# E-P-206-R1_2_Fuel_Cell_Control_Board_to_.net
KiCad netlist of a schematic drawn in EAGLE
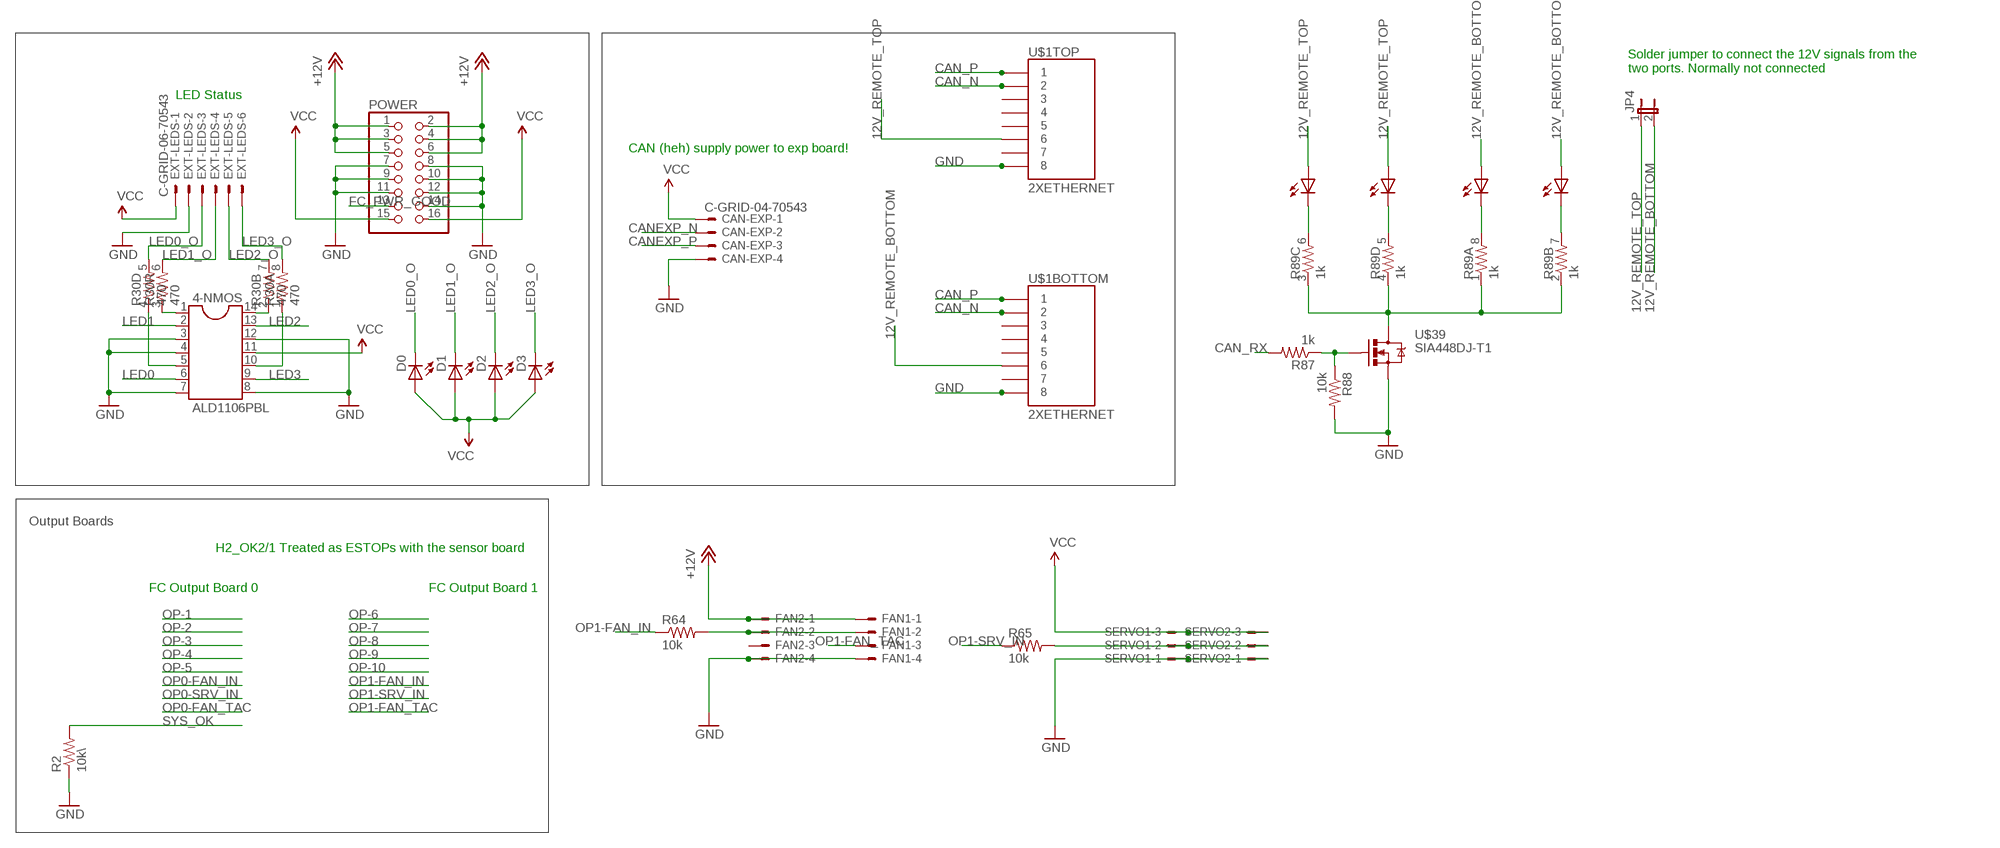
[diagram p0: schematic, sheet 1]
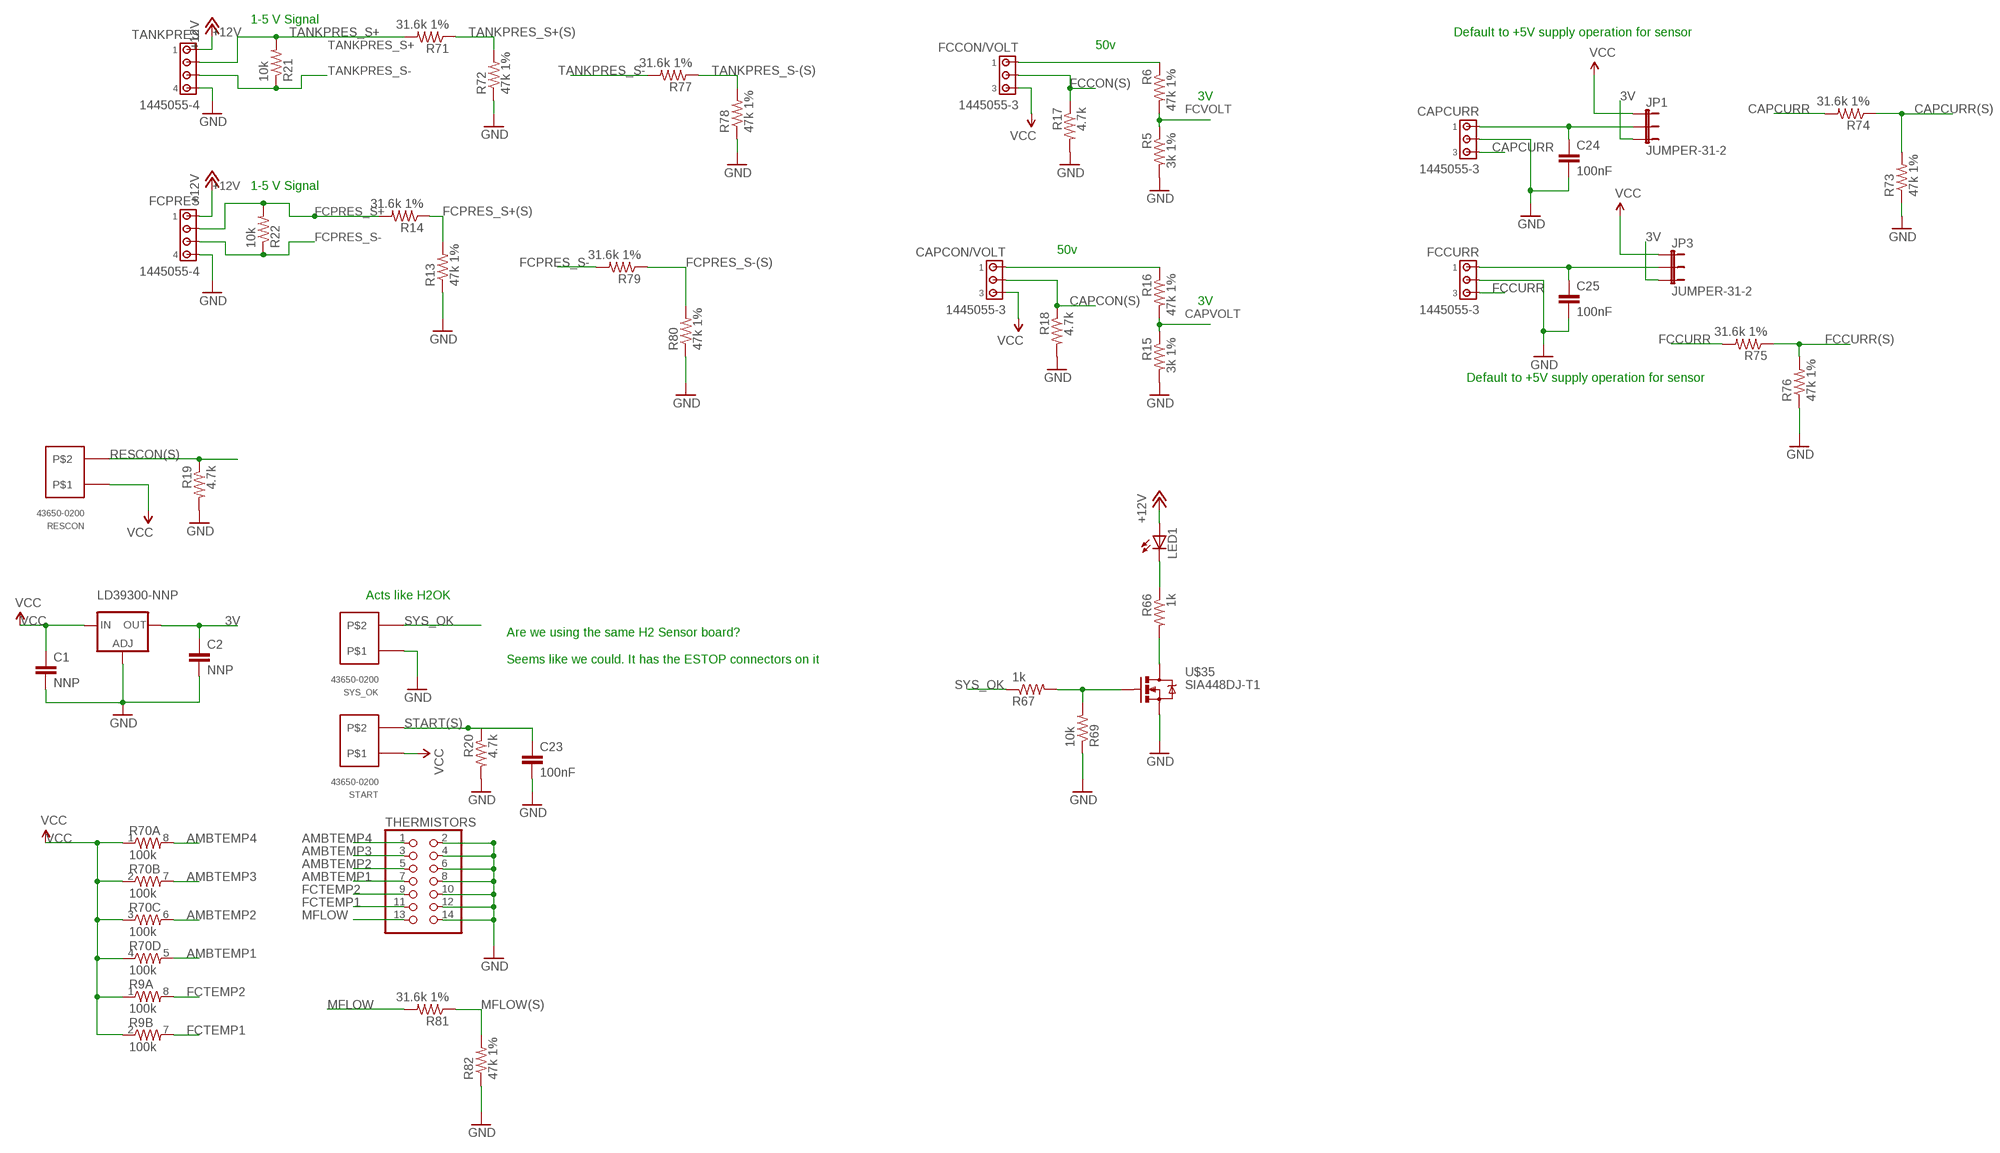
[diagram p1: schematic, sheet 2]
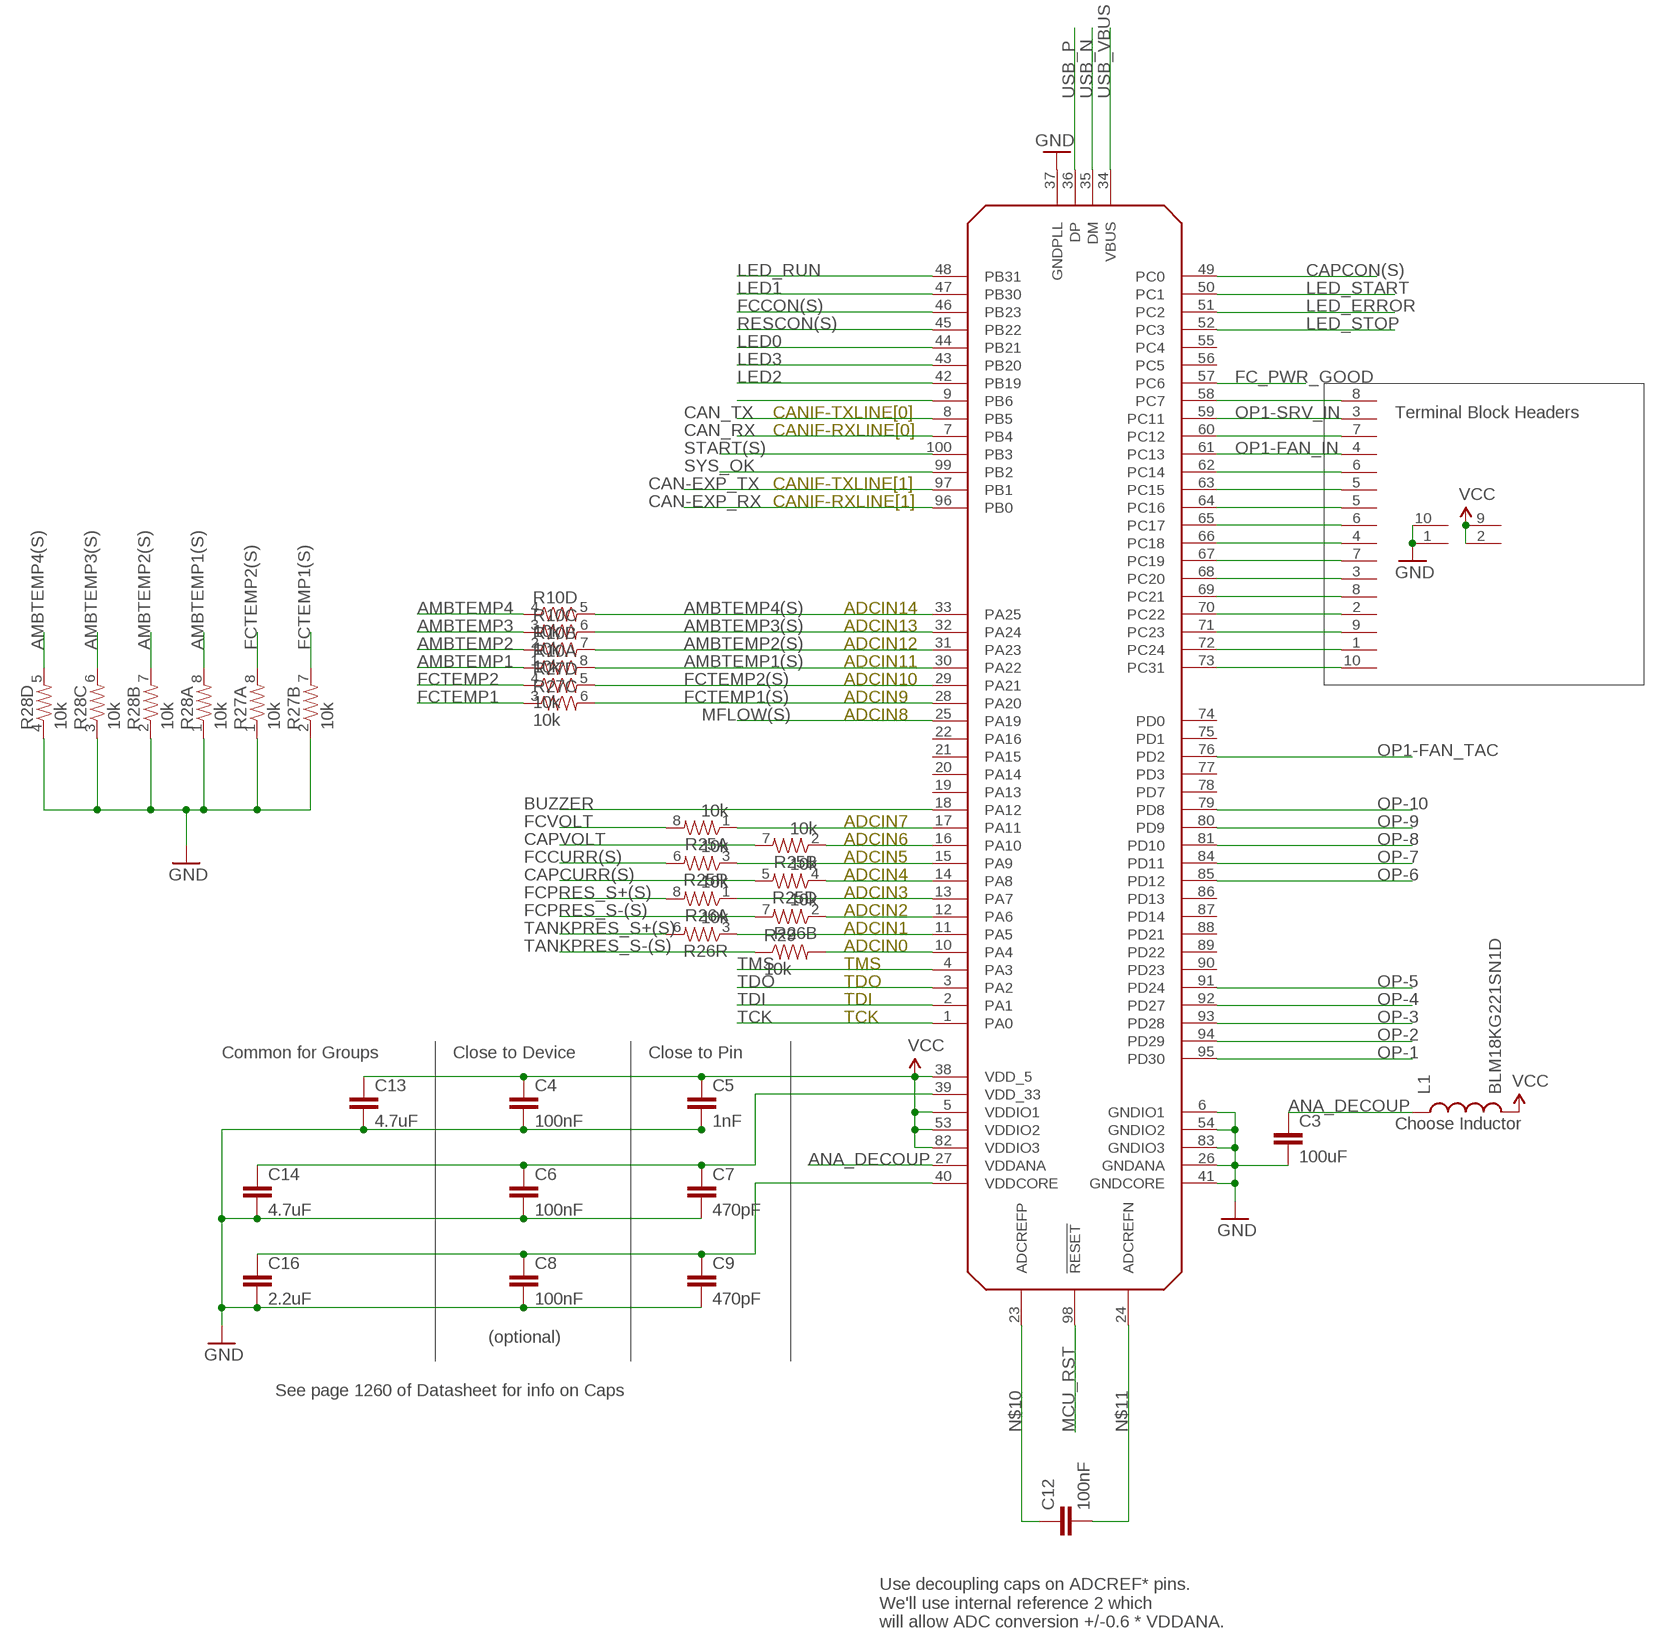
[diagram p2: schematic, sheet 3, part 1 of 2]
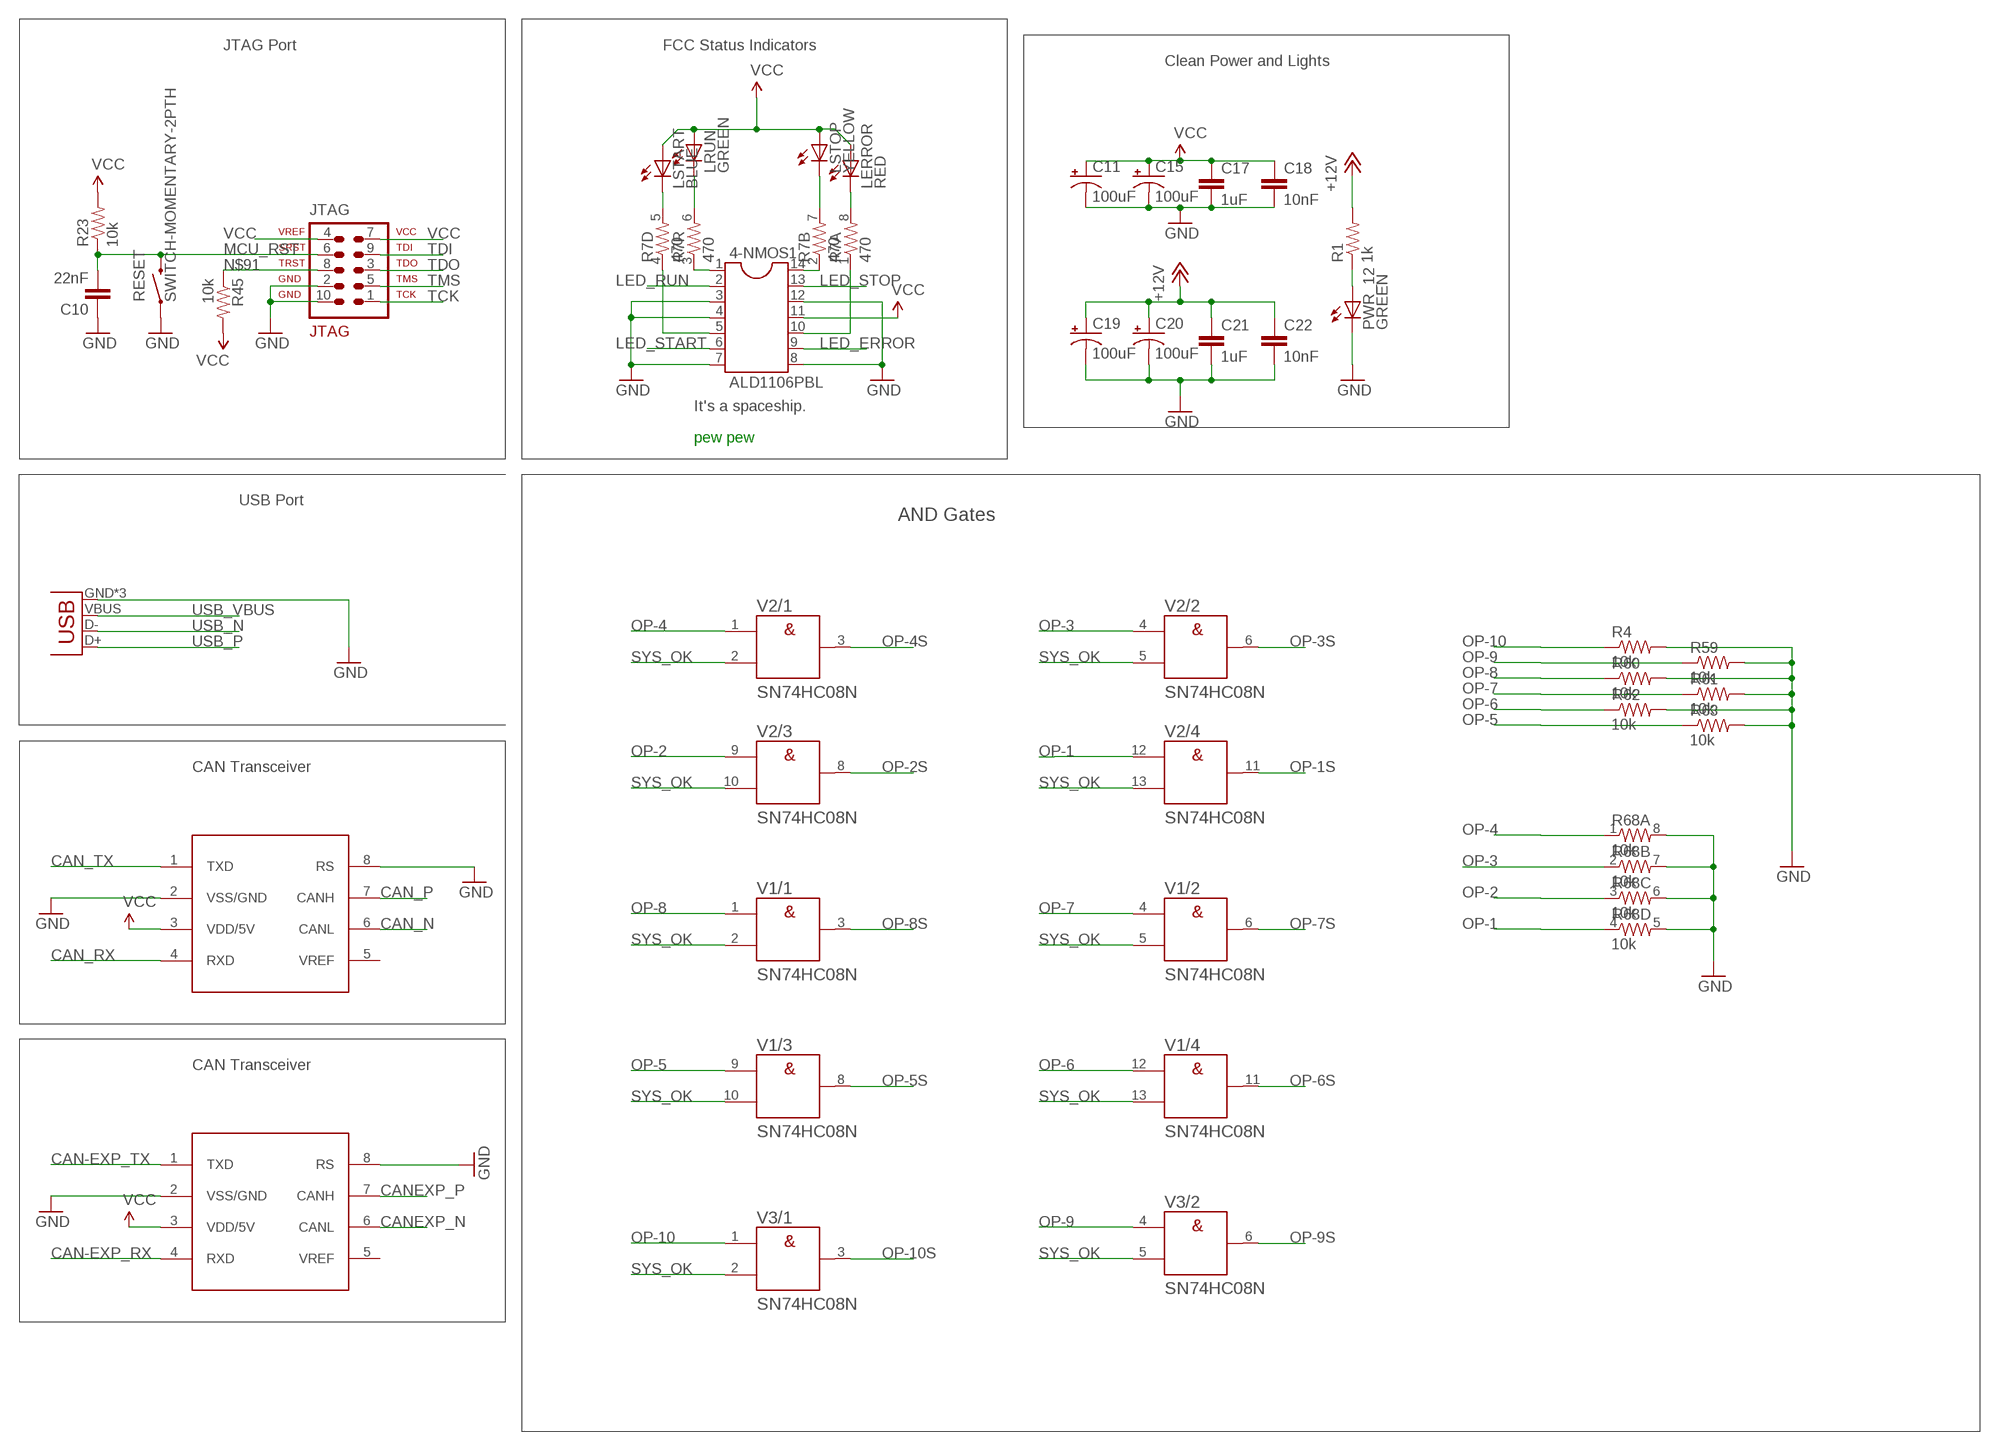
[diagram p3: schematic, sheet 3, part 2 of 2]
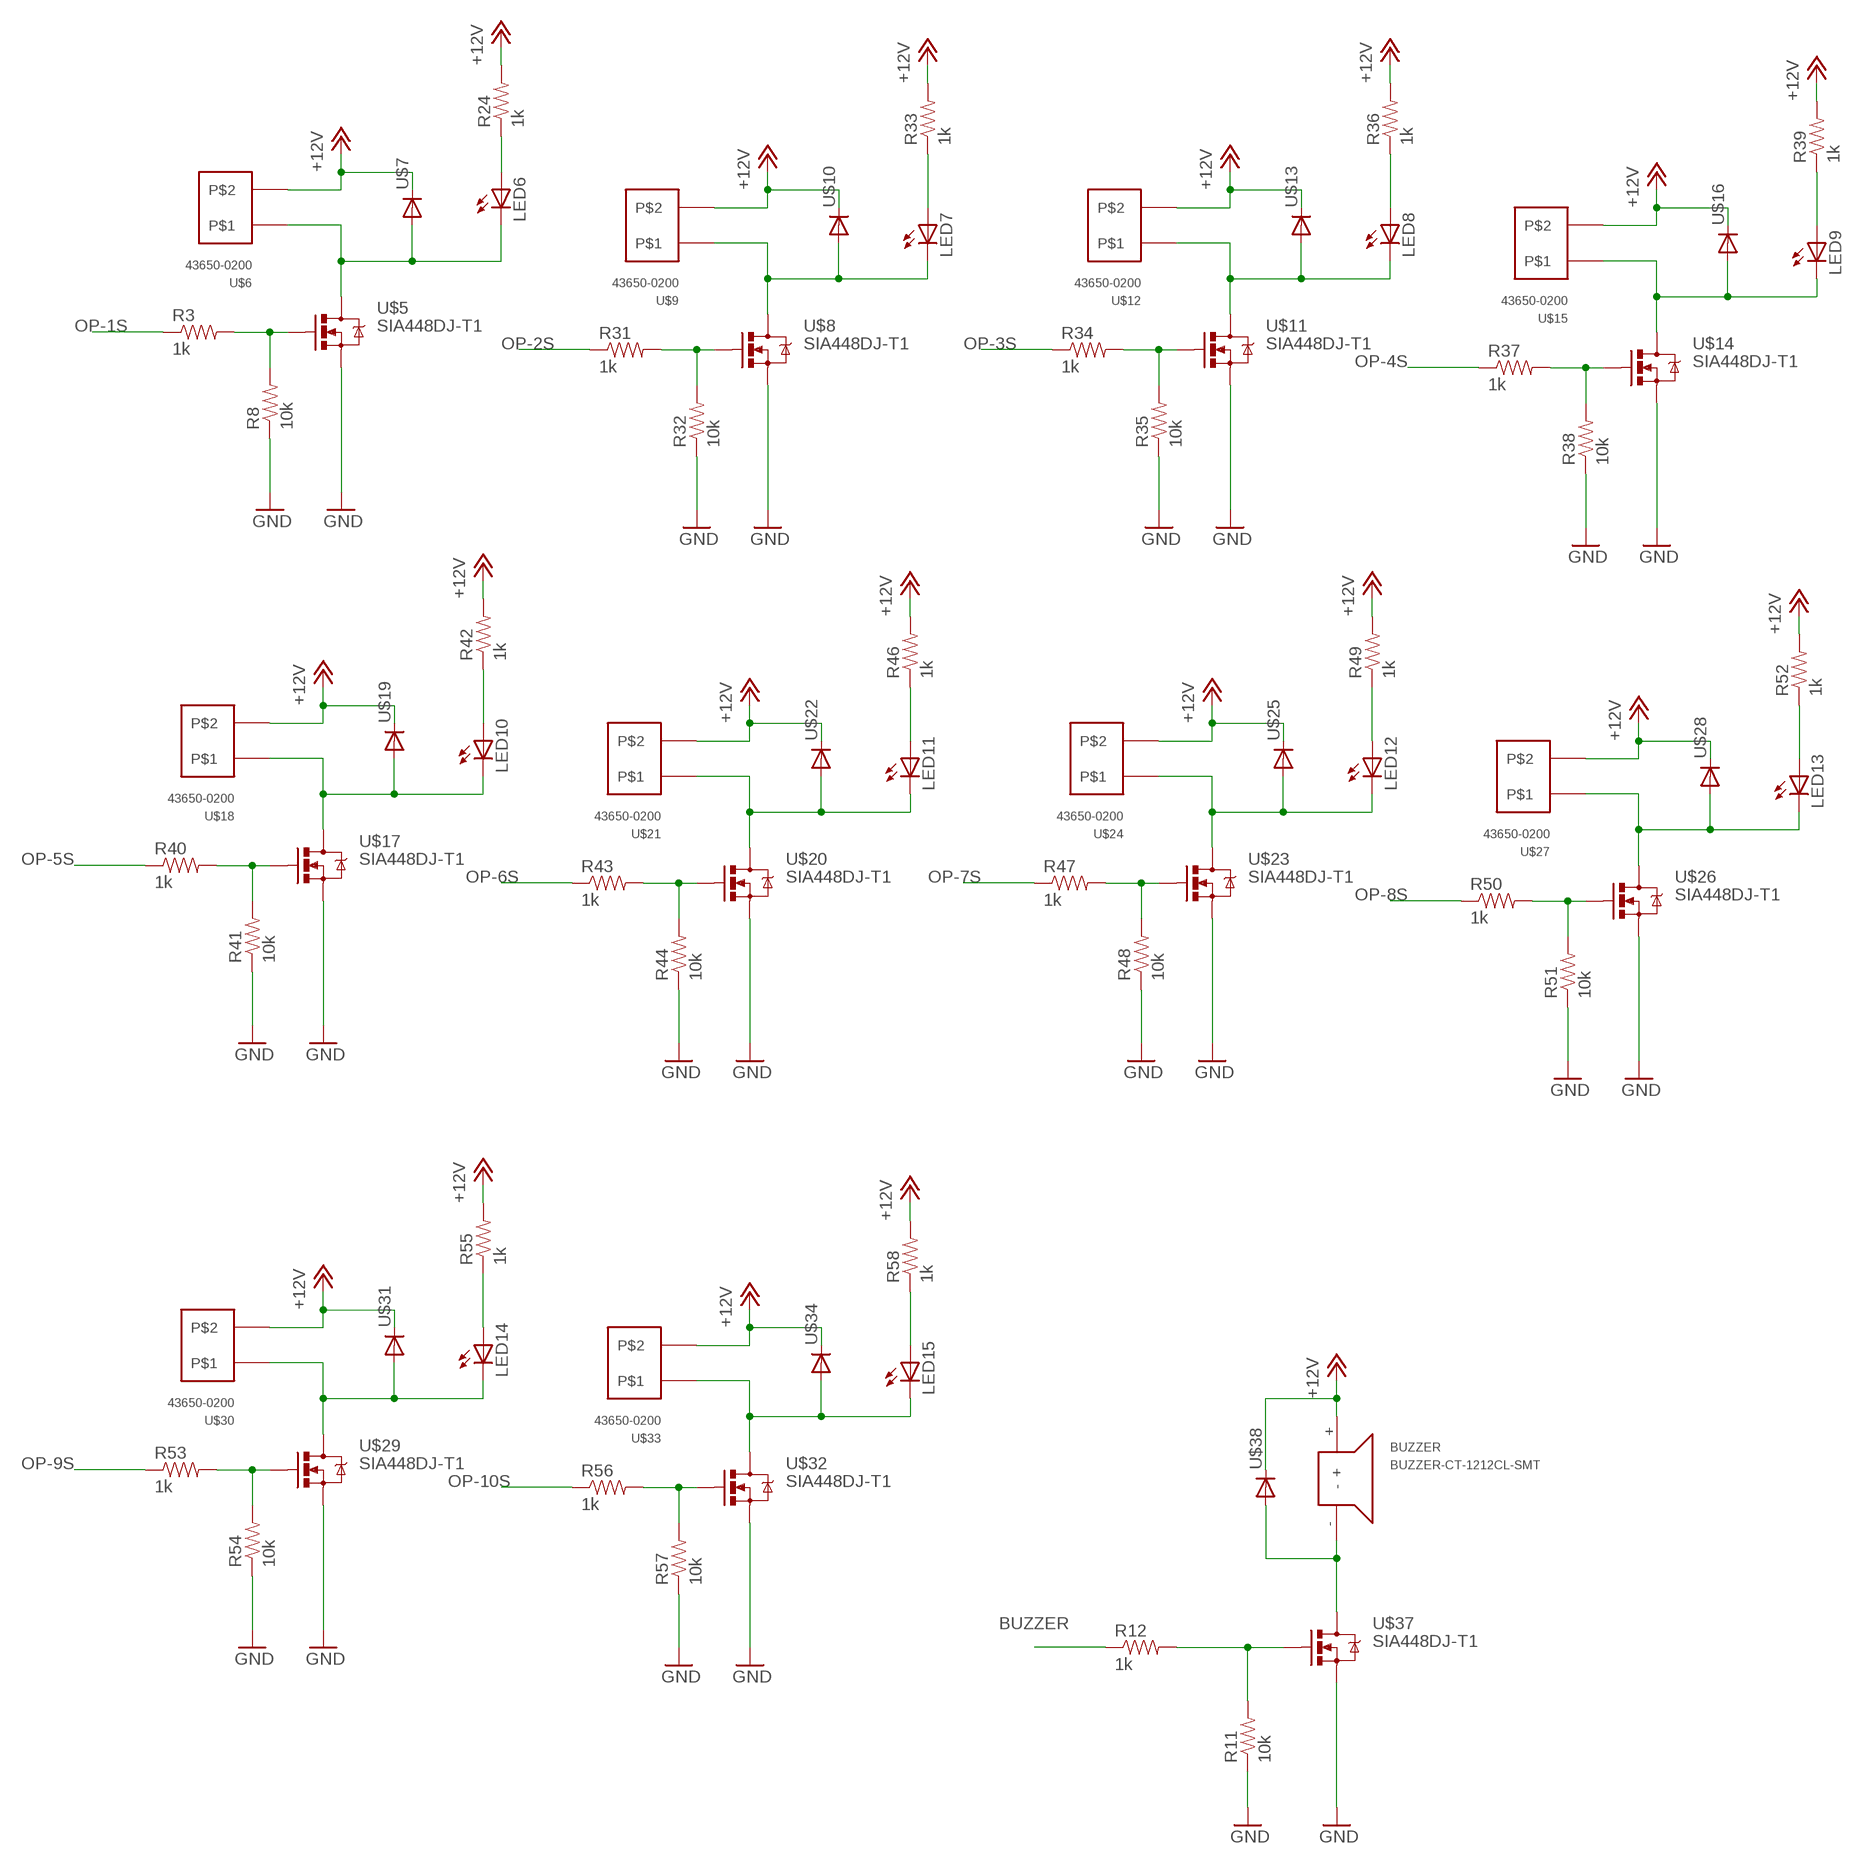
[diagram p4: schematic, sheet 4]

(export (version "E")
  (design (tool "Eeschema 10.0.6"))
  (components
    (comp (ref "4-NMOS")
      (value "ALD1106PBL")
      (footprint "eagle-import:SOIC-14")
      (libsource (lib "eagle-import") (part "DIL14SOIC"))
    )
    (comp (ref "CAN-EXP")
      (value "C-GRID-04-70543")
      (footprint "eagle-import:70543-04")
      (libsource (lib "eagle-import") (part "C-GRID-04-70543"))
    )
    (comp (ref "D0")
      (value "LED1206")
      (footprint "eagle-import:LED-1206")
      (libsource (lib "eagle-import") (part "LED1206"))
    )
    (comp (ref "D1")
      (value "LED1206")
      (footprint "eagle-import:LED-1206")
      (libsource (lib "eagle-import") (part "LED1206"))
    )
    (comp (ref "D2")
      (value "LED1206")
      (footprint "eagle-import:LED-1206")
      (libsource (lib "eagle-import") (part "LED1206"))
    )
    (comp (ref "D3")
      (value "LED1206")
      (footprint "eagle-import:LED-1206")
      (libsource (lib "eagle-import") (part "LED1206"))
    )
    (comp (ref "EXT-LEDS")
      (value "C-GRID-06-70543")
      (footprint "eagle-import:70543-06")
      (libsource (lib "eagle-import") (part "C-GRID-06-70543"))
    )
    (comp (ref "FAN1")
      (value "C-GRID-04-70543")
      (footprint "eagle-import:70543-04")
      (libsource (lib "eagle-import") (part "C-GRID-04-70543"))
    )
    (comp (ref "FAN2")
      (value "C-GRID-04-70543")
      (footprint "eagle-import:70543-04")
      (libsource (lib "eagle-import") (part "C-GRID-04-70543"))
    )
    (comp (ref "JP4")
      (value "JUMPER-2SMD-NO")
      (footprint "eagle-import:SJ_2S-NO")
      (libsource (lib "eagle-import") (part "JUMPER-2SMD-NO"))
    )
    (comp (ref "POWER")
      (value "PINHD-2X8")
      (footprint "eagle-import:2X08")
      (libsource (lib "eagle-import") (part "PINHD-2X8"))
    )
    (comp (ref "R2")
      (value "10k\\")
      (footprint "eagle-import:0603-RES")
      (libsource (lib "eagle-import") (part "RESISTOR0603-RES"))
    )
    (comp (ref "R30")
      (value "470")
      (footprint "eagle-import:0603-ARV")
      (libsource (lib "eagle-import") (part "SparkFun-Resistors_RESISTOR-ARRAY0603-ARV"))
    )
    (comp (ref "R64")
      (value "10k")
      (footprint "eagle-import:0603-RES")
      (libsource (lib "eagle-import") (part "RESISTOR0603-RES"))
    )
    (comp (ref "R65")
      (value "10k")
      (footprint "eagle-import:0603-RES")
      (libsource (lib "eagle-import") (part "RESISTOR0603-RES"))
    )
    (comp (ref "R87")
      (value "1k")
      (footprint "eagle-import:0603-RES")
      (libsource (lib "eagle-import") (part "RESISTOR0603-RES"))
    )
    (comp (ref "R88")
      (value "10k")
      (footprint "eagle-import:0603-RES")
      (libsource (lib "eagle-import") (part "RESISTOR0603-RES"))
    )
    (comp (ref "R89")
      (value "1k")
      (footprint "eagle-import:0603-ARV")
      (libsource (lib "eagle-import") (part "RESISTOR-ARRAY0603-ARV"))
    )
    (comp (ref "SERVO1")
      (value "C-GRID-03-70543")
      (footprint "eagle-import:70543-03")
      (libsource (lib "eagle-import") (part "C-GRID-03-70543"))
    )
    (comp (ref "SERVO2")
      (value "C-GRID-03-70543")
      (footprint "eagle-import:70543-03")
      (libsource (lib "eagle-import") (part "C-GRID-03-70543"))
    )
    (comp (ref "U$1")
      (value "2XETHERNET")
      (footprint "eagle-import:2XETHERNET")
      (libsource (lib "eagle-import") (part "2XETHERNET"))
    )
    (comp (ref "U$39")
      (value "SIA448DJ-T1")
      (footprint "eagle-import:SC70-6L")
      (libsource (lib "eagle-import") (part "SIA426DJ"))
    )
    (comp (ref "C1")
      (value "NNP")
      (footprint "eagle-import:1206")
      (libsource (lib "eagle-import") (part "CAP1206"))
    )
    (comp (ref "C2")
      (value "NNP")
      (footprint "eagle-import:1206")
      (libsource (lib "eagle-import") (part "CAP1206"))
    )
    (comp (ref "C23")
      (value "100nF")
      (footprint "eagle-import:0603-CAP")
      (libsource (lib "eagle-import") (part "CAP0603-CAP"))
    )
    (comp (ref "C24")
      (value "100nF")
      (footprint "eagle-import:0603-CAP")
      (libsource (lib "eagle-import") (part "CAP0603-CAP"))
    )
    (comp (ref "C25")
      (value "100nF")
      (footprint "eagle-import:0603-CAP")
      (libsource (lib "eagle-import") (part "CAP0603-CAP"))
    )
    (comp (ref "CAPCON/VOLT")
      (value "1445055-3")
      (footprint "eagle-import:1445055-3")
      (libsource (lib "eagle-import") (part "1445055-3"))
    )
    (comp (ref "CAPCURR")
      (value "1445055-3")
      (footprint "eagle-import:1445055-3")
      (libsource (lib "eagle-import") (part "1445055-3"))
    )
    (comp (ref "FCCON/VOLT")
      (value "1445055-3")
      (footprint "eagle-import:1445055-3")
      (libsource (lib "eagle-import") (part "1445055-3"))
    )
    (comp (ref "FCCURR")
      (value "1445055-3")
      (footprint "eagle-import:1445055-3")
      (libsource (lib "eagle-import") (part "1445055-3"))
    )
    (comp (ref "FCPRES")
      (value "1445055-4")
      (footprint "eagle-import:1445055-4")
      (libsource (lib "eagle-import") (part "1445055-4"))
    )
    (comp (ref "JP1")
      (value "JUMPER-31-2")
      (footprint "eagle-import:SJ_3_PASTE1&2")
      (libsource (lib "eagle-import") (part "JUMPER-31-2"))
    )
    (comp (ref "JP3")
      (value "JUMPER-31-2")
      (footprint "eagle-import:SJ_3_PASTE1&2")
      (libsource (lib "eagle-import") (part "JUMPER-31-2"))
    )
    (comp (ref "LD39300-NNP")
      (value "LD117ADT50TR")
      (footprint "eagle-import:DPACK")
      (libsource (lib "eagle-import") (part "LD117A?DT50TR"))
    )
    (comp (ref "LED1")
      (value "LED1206")
      (footprint "eagle-import:LED-1206")
      (libsource (lib "eagle-import") (part "LED1206"))
    )
    (comp (ref "R5")
      (value "3k 1%")
      (footprint "eagle-import:0603-RES")
      (libsource (lib "eagle-import") (part "RESISTOR0603-RES"))
    )
    (comp (ref "R6")
      (value "47k 1%")
      (footprint "eagle-import:0603-RES")
      (libsource (lib "eagle-import") (part "RESISTOR0603-RES"))
    )
    (comp (ref "R9")
      (value "100k")
      (footprint "eagle-import:0603-ARV")
      (libsource (lib "eagle-import") (part "RESISTOR-ARRAY0603-ARV"))
    )
    (comp (ref "R13")
      (value "47k 1%")
      (footprint "eagle-import:0603-RES")
      (libsource (lib "eagle-import") (part "RESISTOR0603-RES"))
    )
    (comp (ref "R14")
      (value "31.6k 1%")
      (footprint "eagle-import:0603-RES")
      (libsource (lib "eagle-import") (part "RESISTOR0603-RES"))
    )
    (comp (ref "R15")
      (value "3k 1%")
      (footprint "eagle-import:0603-RES")
      (libsource (lib "eagle-import") (part "RESISTOR0603-RES"))
    )
    (comp (ref "R16")
      (value "47k 1%")
      (footprint "eagle-import:0603-RES")
      (libsource (lib "eagle-import") (part "RESISTOR0603-RES"))
    )
    (comp (ref "R17")
      (value "4.7k")
      (footprint "eagle-import:0603-RES")
      (libsource (lib "eagle-import") (part "RESISTOR0603-RES"))
    )
    (comp (ref "R18")
      (value "4.7k")
      (footprint "eagle-import:0603-RES")
      (libsource (lib "eagle-import") (part "RESISTOR0603-RES"))
    )
    (comp (ref "R19")
      (value "4.7k")
      (footprint "eagle-import:0603-RES")
      (libsource (lib "eagle-import") (part "RESISTOR0603-RES"))
    )
    (comp (ref "R20")
      (value "4.7k")
      (footprint "eagle-import:0603-RES")
      (libsource (lib "eagle-import") (part "RESISTOR0603-RES"))
    )
    (comp (ref "R21")
      (value "10k")
      (footprint "eagle-import:0603-RES")
      (libsource (lib "eagle-import") (part "RESISTOR0603-RES"))
    )
    (comp (ref "R22")
      (value "10k")
      (footprint "eagle-import:0603-RES")
      (libsource (lib "eagle-import") (part "RESISTOR0603-RES"))
    )
    (comp (ref "R66")
      (value "1k")
      (footprint "eagle-import:0603-RES")
      (libsource (lib "eagle-import") (part "RESISTOR0603-RES"))
    )
    (comp (ref "R67")
      (value "1k")
      (footprint "eagle-import:0603-RES")
      (libsource (lib "eagle-import") (part "RESISTOR0603-RES"))
    )
    (comp (ref "R69")
      (value "10k")
      (footprint "eagle-import:0603-RES")
      (libsource (lib "eagle-import") (part "RESISTOR0603-RES"))
    )
    (comp (ref "R70")
      (value "100k")
      (footprint "eagle-import:0603-ARV")
      (libsource (lib "eagle-import") (part "RESISTOR-ARRAY0603-ARV"))
    )
    (comp (ref "R71")
      (value "31.6k 1%")
      (footprint "eagle-import:0603-RES")
      (libsource (lib "eagle-import") (part "RESISTOR0603-RES"))
    )
    (comp (ref "R72")
      (value "47k 1%")
      (footprint "eagle-import:0603-RES")
      (libsource (lib "eagle-import") (part "RESISTOR0603-RES"))
    )
    (comp (ref "R73")
      (value "47k 1%")
      (footprint "eagle-import:0603-RES")
      (libsource (lib "eagle-import") (part "RESISTOR0603-RES"))
    )
    (comp (ref "R74")
      (value "31.6k 1%")
      (footprint "eagle-import:0603-RES")
      (libsource (lib "eagle-import") (part "RESISTOR0603-RES"))
    )
    (comp (ref "R75")
      (value "31.6k 1%")
      (footprint "eagle-import:0603-RES")
      (libsource (lib "eagle-import") (part "RESISTOR0603-RES"))
    )
    (comp (ref "R76")
      (value "47k 1%")
      (footprint "eagle-import:0603-RES")
      (libsource (lib "eagle-import") (part "RESISTOR0603-RES"))
    )
    (comp (ref "R77")
      (value "31.6k 1%")
      (footprint "eagle-import:0603-RES")
      (libsource (lib "eagle-import") (part "RESISTOR0603-RES"))
    )
    (comp (ref "R78")
      (value "47k 1%")
      (footprint "eagle-import:0603-RES")
      (libsource (lib "eagle-import") (part "RESISTOR0603-RES"))
    )
    (comp (ref "R79")
      (value "31.6k 1%")
      (footprint "eagle-import:0603-RES")
      (libsource (lib "eagle-import") (part "RESISTOR0603-RES"))
    )
    (comp (ref "R80")
      (value "47k 1%")
      (footprint "eagle-import:0603-RES")
      (libsource (lib "eagle-import") (part "RESISTOR0603-RES"))
    )
    (comp (ref "R81")
      (value "31.6k 1%")
      (footprint "eagle-import:0603-RES")
      (libsource (lib "eagle-import") (part "RESISTOR0603-RES"))
    )
    (comp (ref "R82")
      (value "47k 1%")
      (footprint "eagle-import:0603-RES")
      (libsource (lib "eagle-import") (part "RESISTOR0603-RES"))
    )
    (comp (ref "RESCON")
      (value "43650-0200")
      (footprint "eagle-import:43650-0200")
      (libsource (lib "eagle-import") (part "43650-0200"))
    )
    (comp (ref "START")
      (value "43650-0200")
      (footprint "eagle-import:43650-0200")
      (libsource (lib "eagle-import") (part "43650-0200"))
    )
    (comp (ref "SYS_OK")
      (value "43650-0200")
      (footprint "eagle-import:43650-0200")
      (libsource (lib "eagle-import") (part "43650-0200"))
    )
    (comp (ref "TANKPRES")
      (value "1445055-4")
      (footprint "eagle-import:1445055-4")
      (libsource (lib "eagle-import") (part "1445055-4"))
    )
    (comp (ref "THERMISTORS")
      (value "PINHD-2X7")
      (footprint "eagle-import:2X07")
      (libsource (lib "eagle-import") (part "PINHD-2X7"))
    )
    (comp (ref "U$35")
      (value "SIA448DJ-T1")
      (footprint "eagle-import:SC70-6L")
      (libsource (lib "eagle-import") (part "SIA426DJ"))
    )
    (comp (ref "BUZZER")
      (value "BUZZER-CT-1212CL-SMT")
      (footprint "eagle-import:CT-1212CL-SMT")
      (libsource (lib "eagle-import") (part "BUZZER-CT-1212CL-SMT"))
    )
    (comp (ref "LED6")
      (value "LED1206")
      (footprint "eagle-import:LED-1206")
      (libsource (lib "eagle-import") (part "LED1206"))
    )
    (comp (ref "LED7")
      (value "LED1206")
      (footprint "eagle-import:LED-1206")
      (libsource (lib "eagle-import") (part "LED1206"))
    )
    (comp (ref "LED8")
      (value "LED1206")
      (footprint "eagle-import:LED-1206")
      (libsource (lib "eagle-import") (part "LED1206"))
    )
    (comp (ref "LED9")
      (value "LED1206")
      (footprint "eagle-import:LED-1206")
      (libsource (lib "eagle-import") (part "LED1206"))
    )
    (comp (ref "LED10")
      (value "LED1206")
      (footprint "eagle-import:LED-1206")
      (libsource (lib "eagle-import") (part "LED1206"))
    )
    (comp (ref "LED11")
      (value "LED1206")
      (footprint "eagle-import:LED-1206")
      (libsource (lib "eagle-import") (part "LED1206"))
    )
    (comp (ref "LED12")
      (value "LED1206")
      (footprint "eagle-import:LED-1206")
      (libsource (lib "eagle-import") (part "LED1206"))
    )
    (comp (ref "LED13")
      (value "LED1206")
      (footprint "eagle-import:LED-1206")
      (libsource (lib "eagle-import") (part "LED1206"))
    )
    (comp (ref "LED14")
      (value "LED1206")
      (footprint "eagle-import:LED-1206")
      (libsource (lib "eagle-import") (part "LED1206"))
    )
    (comp (ref "LED15")
      (value "LED1206")
      (footprint "eagle-import:LED-1206")
      (libsource (lib "eagle-import") (part "LED1206"))
    )
    (comp (ref "R3")
      (value "1k")
      (footprint "eagle-import:0603-RES")
      (libsource (lib "eagle-import") (part "RESISTOR0603-RES"))
    )
    (comp (ref "R8")
      (value "10k")
      (footprint "eagle-import:0603-RES")
      (libsource (lib "eagle-import") (part "RESISTOR0603-RES"))
    )
    (comp (ref "R11")
      (value "10k")
      (footprint "eagle-import:0603-RES")
      (libsource (lib "eagle-import") (part "RESISTOR0603-RES"))
    )
    (comp (ref "R12")
      (value "1k")
      (footprint "eagle-import:0603-RES")
      (libsource (lib "eagle-import") (part "RESISTOR0603-RES"))
    )
    (comp (ref "R24")
      (value "1k")
      (footprint "eagle-import:0603-RES")
      (libsource (lib "eagle-import") (part "RESISTOR0603-RES"))
    )
    (comp (ref "R31")
      (value "1k")
      (footprint "eagle-import:0603-RES")
      (libsource (lib "eagle-import") (part "RESISTOR0603-RES"))
    )
    (comp (ref "R32")
      (value "10k")
      (footprint "eagle-import:0603-RES")
      (libsource (lib "eagle-import") (part "RESISTOR0603-RES"))
    )
    (comp (ref "R33")
      (value "1k")
      (footprint "eagle-import:0603-RES")
      (libsource (lib "eagle-import") (part "RESISTOR0603-RES"))
    )
    (comp (ref "R34")
      (value "1k")
      (footprint "eagle-import:0603-RES")
      (libsource (lib "eagle-import") (part "RESISTOR0603-RES"))
    )
    (comp (ref "R35")
      (value "10k")
      (footprint "eagle-import:0603-RES")
      (libsource (lib "eagle-import") (part "RESISTOR0603-RES"))
    )
    (comp (ref "R36")
      (value "1k")
      (footprint "eagle-import:0603-RES")
      (libsource (lib "eagle-import") (part "RESISTOR0603-RES"))
    )
    (comp (ref "R37")
      (value "1k")
      (footprint "eagle-import:0603-RES")
      (libsource (lib "eagle-import") (part "RESISTOR0603-RES"))
    )
    (comp (ref "R38")
      (value "10k")
      (footprint "eagle-import:0603-RES")
      (libsource (lib "eagle-import") (part "RESISTOR0603-RES"))
    )
    (comp (ref "R39")
      (value "1k")
      (footprint "eagle-import:0603-RES")
      (libsource (lib "eagle-import") (part "RESISTOR0603-RES"))
    )
    (comp (ref "R40")
      (value "1k")
      (footprint "eagle-import:0603-RES")
      (libsource (lib "eagle-import") (part "RESISTOR0603-RES"))
    )
    (comp (ref "R41")
      (value "10k")
      (footprint "eagle-import:0603-RES")
      (libsource (lib "eagle-import") (part "RESISTOR0603-RES"))
    )
    (comp (ref "R42")
      (value "1k")
      (footprint "eagle-import:0603-RES")
      (libsource (lib "eagle-import") (part "RESISTOR0603-RES"))
    )
    (comp (ref "R43")
      (value "1k")
      (footprint "eagle-import:0603-RES")
      (libsource (lib "eagle-import") (part "RESISTOR0603-RES"))
    )
    (comp (ref "R44")
      (value "10k")
      (footprint "eagle-import:0603-RES")
      (libsource (lib "eagle-import") (part "RESISTOR0603-RES"))
    )
    (comp (ref "R46")
      (value "1k")
      (footprint "eagle-import:0603-RES")
      (libsource (lib "eagle-import") (part "RESISTOR0603-RES"))
    )
    (comp (ref "R47")
      (value "1k")
      (footprint "eagle-import:0603-RES")
      (libsource (lib "eagle-import") (part "RESISTOR0603-RES"))
    )
    (comp (ref "R48")
      (value "10k")
      (footprint "eagle-import:0603-RES")
      (libsource (lib "eagle-import") (part "RESISTOR0603-RES"))
    )
    (comp (ref "R49")
      (value "1k")
      (footprint "eagle-import:0603-RES")
      (libsource (lib "eagle-import") (part "RESISTOR0603-RES"))
    )
    (comp (ref "R50")
      (value "1k")
      (footprint "eagle-import:0603-RES")
      (libsource (lib "eagle-import") (part "RESISTOR0603-RES"))
    )
    (comp (ref "R51")
      (value "10k")
      (footprint "eagle-import:0603-RES")
      (libsource (lib "eagle-import") (part "RESISTOR0603-RES"))
    )
    (comp (ref "R52")
      (value "1k")
      (footprint "eagle-import:0603-RES")
      (libsource (lib "eagle-import") (part "RESISTOR0603-RES"))
    )
    (comp (ref "R53")
      (value "1k")
      (footprint "eagle-import:0603-RES")
      (libsource (lib "eagle-import") (part "RESISTOR0603-RES"))
    )
    (comp (ref "R54")
      (value "10k")
      (footprint "eagle-import:0603-RES")
      (libsource (lib "eagle-import") (part "RESISTOR0603-RES"))
    )
    (comp (ref "R55")
      (value "1k")
      (footprint "eagle-import:0603-RES")
      (libsource (lib "eagle-import") (part "RESISTOR0603-RES"))
    )
    (comp (ref "R56")
      (value "1k")
      (footprint "eagle-import:0603-RES")
      (libsource (lib "eagle-import") (part "RESISTOR0603-RES"))
    )
    (comp (ref "R57")
      (value "10k")
      (footprint "eagle-import:0603-RES")
      (libsource (lib "eagle-import") (part "RESISTOR0603-RES"))
    )
    (comp (ref "R58")
      (value "1k")
      (footprint "eagle-import:0603-RES")
      (libsource (lib "eagle-import") (part "RESISTOR0603-RES"))
    )
    (comp (ref "U$5")
      (value "SIA448DJ-T1")
      (footprint "eagle-import:SC70-6L")
      (libsource (lib "eagle-import") (part "SIA426DJ"))
    )
    (comp (ref "U$6")
      (value "43650-0200")
      (footprint "eagle-import:43650-0200")
      (libsource (lib "eagle-import") (part "43650-0200"))
    )
    (comp (ref "U$7")
      (value "DIODE-DO214AC")
      (footprint "eagle-import:DO214AC")
      (libsource (lib "eagle-import") (part "DIODE-DO214AC"))
    )
    (comp (ref "U$8")
      (value "SIA448DJ-T1")
      (footprint "eagle-import:SC70-6L")
      (libsource (lib "eagle-import") (part "SIA426DJ"))
    )
    (comp (ref "U$9")
      (value "43650-0200")
      (footprint "eagle-import:43650-0200")
      (libsource (lib "eagle-import") (part "43650-0200"))
    )
    (comp (ref "U$10")
      (value "DIODE-DO214AC")
      (footprint "eagle-import:DO214AC")
      (libsource (lib "eagle-import") (part "DIODE-DO214AC"))
    )
    (comp (ref "U$11")
      (value "SIA448DJ-T1")
      (footprint "eagle-import:SC70-6L")
      (libsource (lib "eagle-import") (part "SIA426DJ"))
    )
    (comp (ref "U$12")
      (value "43650-0200")
      (footprint "eagle-import:43650-0200")
      (libsource (lib "eagle-import") (part "43650-0200"))
    )
    (comp (ref "U$13")
      (value "DIODE-DO214AC")
      (footprint "eagle-import:DO214AC")
      (libsource (lib "eagle-import") (part "DIODE-DO214AC"))
    )
    (comp (ref "U$14")
      (value "SIA448DJ-T1")
      (footprint "eagle-import:SC70-6L")
      (libsource (lib "eagle-import") (part "SIA426DJ"))
    )
    (comp (ref "U$15")
      (value "43650-0200")
      (footprint "eagle-import:43650-0200")
      (libsource (lib "eagle-import") (part "43650-0200"))
    )
    (comp (ref "U$16")
      (value "DIODE-DO214AC")
      (footprint "eagle-import:DO214AC")
      (libsource (lib "eagle-import") (part "DIODE-DO214AC"))
    )
    (comp (ref "U$17")
      (value "SIA448DJ-T1")
      (footprint "eagle-import:SC70-6L")
      (libsource (lib "eagle-import") (part "SIA426DJ"))
    )
    (comp (ref "U$18")
      (value "43650-0200")
      (footprint "eagle-import:43650-0200")
      (libsource (lib "eagle-import") (part "43650-0200"))
    )
    (comp (ref "U$19")
      (value "DIODE-DO214AC")
      (footprint "eagle-import:DO214AC")
      (libsource (lib "eagle-import") (part "DIODE-DO214AC"))
    )
    (comp (ref "U$20")
      (value "SIA448DJ-T1")
      (footprint "eagle-import:SC70-6L")
      (libsource (lib "eagle-import") (part "SIA426DJ"))
    )
    (comp (ref "U$21")
      (value "43650-0200")
      (footprint "eagle-import:43650-0200")
      (libsource (lib "eagle-import") (part "43650-0200"))
    )
    (comp (ref "U$22")
      (value "DIODE-DO214AC")
      (footprint "eagle-import:DO214AC")
      (libsource (lib "eagle-import") (part "DIODE-DO214AC"))
    )
    (comp (ref "U$23")
      (value "SIA448DJ-T1")
      (footprint "eagle-import:SC70-6L")
      (libsource (lib "eagle-import") (part "SIA426DJ"))
    )
    (comp (ref "U$24")
      (value "43650-0200")
      (footprint "eagle-import:43650-0200")
      (libsource (lib "eagle-import") (part "43650-0200"))
    )
    (comp (ref "U$25")
      (value "DIODE-DO214AC")
      (footprint "eagle-import:DO214AC")
      (libsource (lib "eagle-import") (part "DIODE-DO214AC"))
    )
    (comp (ref "U$26")
      (value "SIA448DJ-T1")
      (footprint "eagle-import:SC70-6L")
      (libsource (lib "eagle-import") (part "SIA426DJ"))
    )
    (comp (ref "U$27")
      (value "43650-0200")
      (footprint "eagle-import:43650-0200")
      (libsource (lib "eagle-import") (part "43650-0200"))
    )
    (comp (ref "U$28")
      (value "DIODE-DO214AC")
      (footprint "eagle-import:DO214AC")
      (libsource (lib "eagle-import") (part "DIODE-DO214AC"))
    )
    (comp (ref "U$29")
      (value "SIA448DJ-T1")
      (footprint "eagle-import:SC70-6L")
      (libsource (lib "eagle-import") (part "SIA426DJ"))
    )
    (comp (ref "U$30")
      (value "43650-0200")
      (footprint "eagle-import:43650-0200")
      (libsource (lib "eagle-import") (part "43650-0200"))
    )
    (comp (ref "U$31")
      (value "DIODE-DO214AC")
      (footprint "eagle-import:DO214AC")
      (libsource (lib "eagle-import") (part "DIODE-DO214AC"))
    )
    (comp (ref "U$32")
      (value "SIA448DJ-T1")
      (footprint "eagle-import:SC70-6L")
      (libsource (lib "eagle-import") (part "SIA426DJ"))
    )
    (comp (ref "U$33")
      (value "43650-0200")
      (footprint "eagle-import:43650-0200")
      (libsource (lib "eagle-import") (part "43650-0200"))
    )
    (comp (ref "U$34")
      (value "DIODE-DO214AC")
      (footprint "eagle-import:DO214AC")
      (libsource (lib "eagle-import") (part "DIODE-DO214AC"))
    )
    (comp (ref "U$37")
      (value "SIA448DJ-T1")
      (footprint "eagle-import:SC70-6L")
      (libsource (lib "eagle-import") (part "SIA426DJ"))
    )
    (comp (ref "U$38")
      (value "DIODE-DO214AC")
      (footprint "eagle-import:DO214AC")
      (libsource (lib "eagle-import") (part "DIODE-DO214AC"))
    )
    (comp (ref "4-NMOS1")
      (value "ALD1106PBL")
      (footprint "eagle-import:SOIC-14")
      (libsource (lib "eagle-import") (part "DIL14SOIC"))
    )
    (comp (ref "C3")
      (value "100uF")
      (footprint "eagle-import:0805")
      (libsource (lib "eagle-import") (part "CAP0805"))
    )
    (comp (ref "C4")
      (value "100nF")
      (footprint "eagle-import:0603-CAP")
      (libsource (lib "eagle-import") (part "CAP0603-CAP"))
    )
    (comp (ref "C5")
      (value "1nF")
      (footprint "eagle-import:0603-CAP")
      (libsource (lib "eagle-import") (part "CAP0603-CAP"))
    )
    (comp (ref "C6")
      (value "100nF")
      (footprint "eagle-import:0603-CAP")
      (libsource (lib "eagle-import") (part "CAP0603-CAP"))
    )
    (comp (ref "C7")
      (value "470pF")
      (footprint "eagle-import:0603-CAP")
      (libsource (lib "eagle-import") (part "CAP0603-CAP"))
    )
    (comp (ref "C8")
      (value "100nF")
      (footprint "eagle-import:0603-CAP")
      (libsource (lib "eagle-import") (part "CAP0603-CAP"))
    )
    (comp (ref "C9")
      (value "470pF")
      (footprint "eagle-import:0603-CAP")
      (libsource (lib "eagle-import") (part "CAP0603-CAP"))
    )
    (comp (ref "C10")
      (value "22nF")
      (footprint "eagle-import:0603-CAP")
      (libsource (lib "eagle-import") (part "CAP0603-CAP"))
    )
    (comp (ref "C11")
      (value "100uF")
      (footprint "eagle-import:PANASONIC_C")
      (libsource (lib "eagle-import") (part "CAP_POLC"))
    )
    (comp (ref "C12")
      (value "100nF")
      (footprint "eagle-import:0805")
      (libsource (lib "eagle-import") (part "SparkFun-Capacitors_CAP0805"))
    )
    (comp (ref "C13")
      (value "4.7uF")
      (footprint "eagle-import:0805")
      (libsource (lib "eagle-import") (part "SparkFun-Capacitors_CAP0805"))
    )
    (comp (ref "C14")
      (value "4.7uF")
      (footprint "eagle-import:0805")
      (libsource (lib "eagle-import") (part "SparkFun-Capacitors_CAP0805"))
    )
    (comp (ref "C15")
      (value "100uF")
      (footprint "eagle-import:PANASONIC_C")
      (libsource (lib "eagle-import") (part "CAP_POLC"))
    )
    (comp (ref "C16")
      (value "2.2uF")
      (footprint "eagle-import:0805")
      (libsource (lib "eagle-import") (part "SparkFun-Capacitors_CAP0805"))
    )
    (comp (ref "C17")
      (value "1uF")
      (footprint "eagle-import:0805")
      (libsource (lib "eagle-import") (part "SparkFun-Capacitors_CAP0805"))
    )
    (comp (ref "C18")
      (value "10nF")
      (footprint "eagle-import:0603-CAP")
      (libsource (lib "eagle-import") (part "CAP0603-CAP"))
    )
    (comp (ref "C19")
      (value "100uF")
      (footprint "eagle-import:PANASONIC_C")
      (libsource (lib "eagle-import") (part "CAP_POLC"))
    )
    (comp (ref "C20")
      (value "100uF")
      (footprint "eagle-import:PANASONIC_C")
      (libsource (lib "eagle-import") (part "CAP_POLC"))
    )
    (comp (ref "C21")
      (value "1uF")
      (footprint "eagle-import:0805")
      (libsource (lib "eagle-import") (part "SparkFun-Capacitors_CAP0805"))
    )
    (comp (ref "C22")
      (value "10nF")
      (footprint "eagle-import:0603-CAP")
      (libsource (lib "eagle-import") (part "CAP0603-CAP"))
    )
    (comp (ref "JP2")
      (value "USB")
      (footprint "eagle-import:USB-MICROB")
      (libsource (lib "eagle-import") (part "USB-MICROB"))
    )
    (comp (ref "JTAG")
      (value "2x5")
      (footprint "eagle-import:AVR-JTAG-10")
      (libsource (lib "eagle-import") (part "AVR-JTAG-10"))
    )
    (comp (ref "L1")
      (value "BLM18KG221SN1D")
      (footprint "eagle-import:0603")
      (libsource (lib "eagle-import") (part "INDUCTOR0603"))
    )
    (comp (ref "LERROR")
      (value "RED")
      (footprint "eagle-import:LED-1206")
      (libsource (lib "eagle-import") (part "LED1206"))
    )
    (comp (ref "LRUN")
      (value "GREEN")
      (footprint "eagle-import:LED-1206")
      (libsource (lib "eagle-import") (part "LED1206"))
    )
    (comp (ref "LSTART")
      (value "BLUE")
      (footprint "eagle-import:LED-1206")
      (libsource (lib "eagle-import") (part "LED1206"))
    )
    (comp (ref "LSTOP")
      (value "YELLOW")
      (footprint "eagle-import:LED-1206")
      (libsource (lib "eagle-import") (part "LED1206"))
    )
    (comp (ref "MCU")
      (value "AT32UC3C1512")
      (footprint "eagle-import:TQFP100")
      (libsource (lib "eagle-import") (part "AT32UC3C1512"))
    )
    (comp (ref "PWR_12")
      (value "GREEN")
      (footprint "eagle-import:LED-1206")
      (libsource (lib "eagle-import") (part "SparkFun-LED_LED1206"))
    )
    (comp (ref "R1")
      (value "1k")
      (footprint "eagle-import:0603-RES")
      (libsource (lib "eagle-import") (part "RESISTOR0603-RES"))
    )
    (comp (ref "R4")
      (value "10k")
      (footprint "eagle-import:0603-RES")
      (libsource (lib "eagle-import") (part "RESISTOR0603-RES"))
    )
    (comp (ref "R7")
      (value "470")
      (footprint "eagle-import:0603-ARV")
      (libsource (lib "eagle-import") (part "SparkFun-Resistors_RESISTOR-ARRAY0603-ARV"))
    )
    (comp (ref "R10")
      (value "10k")
      (footprint "eagle-import:0603-ARV")
      (libsource (lib "eagle-import") (part "RESISTOR-ARRAY0603-ARV"))
    )
    (comp (ref "R23")
      (value "10k")
      (footprint "eagle-import:0603-RES")
      (libsource (lib "eagle-import") (part "RESISTOR0603-RES"))
    )
    (comp (ref "R25")
      (value "10k")
      (footprint "eagle-import:0603-ARV")
      (libsource (lib "eagle-import") (part "SparkFun-Resistors_RESISTOR-ARRAY0603-ARV"))
    )
    (comp (ref "R26")
      (value "10k")
      (footprint "eagle-import:0603-ARV")
      (libsource (lib "eagle-import") (part "SparkFun-Resistors_RESISTOR-ARRAY0603-ARV"))
    )
    (comp (ref "R27")
      (value "10k")
      (footprint "eagle-import:0603-ARV")
      (libsource (lib "eagle-import") (part "RESISTOR-ARRAY0603-ARV"))
    )
    (comp (ref "R28")
      (value "10k")
      (footprint "eagle-import:0603-ARV")
      (libsource (lib "eagle-import") (part "RESISTOR-ARRAY0603-ARV"))
    )
    (comp (ref "R29")
      (value "10k")
      (footprint "eagle-import:0603-RES")
      (libsource (lib "eagle-import") (part "RESISTOR0603-RES"))
    )
    (comp (ref "R45")
      (value "10k")
      (footprint "eagle-import:0603-RES")
      (libsource (lib "eagle-import") (part "RESISTOR0603-RES"))
    )
    (comp (ref "R59")
      (value "10k")
      (footprint "eagle-import:0603-RES")
      (libsource (lib "eagle-import") (part "RESISTOR0603-RES"))
    )
    (comp (ref "R60")
      (value "10k")
      (footprint "eagle-import:0603-RES")
      (libsource (lib "eagle-import") (part "RESISTOR0603-RES"))
    )
    (comp (ref "R61")
      (value "10k")
      (footprint "eagle-import:0603-RES")
      (libsource (lib "eagle-import") (part "RESISTOR0603-RES"))
    )
    (comp (ref "R62")
      (value "10k")
      (footprint "eagle-import:0603-RES")
      (libsource (lib "eagle-import") (part "RESISTOR0603-RES"))
    )
    (comp (ref "R63")
      (value "10k")
      (footprint "eagle-import:0603-RES")
      (libsource (lib "eagle-import") (part "RESISTOR0603-RES"))
    )
    (comp (ref "R68")
      (value "10k")
      (footprint "eagle-import:0603-ARV")
      (libsource (lib "eagle-import") (part "RESISTOR-ARRAY0603-ARV"))
    )
    (comp (ref "RESET")
      (value "SWITCH-MOMENTARY-2PTH")
      (footprint "eagle-import:TACTILE-PTH")
      (libsource (lib "eagle-import") (part "SWITCH-MOMENTARY-2PTH"))
    )
    (comp (ref "U$2")
      (value "10X1PCBBLOCK")
      (footprint "eagle-import:10X1PCBBLOCK")
      (libsource (lib "eagle-import") (part "10X1PCBBLOCK"))
    )
    (comp (ref "U$3")
      (value "10X1PCBBLOCK")
      (footprint "eagle-import:10X1PCBBLOCK")
      (libsource (lib "eagle-import") (part "10X1PCBBLOCK"))
    )
    (comp (ref "U$4")
      (value "MCP2551")
      (footprint "eagle-import:8-SOIC")
      (libsource (lib "eagle-import") (part "MCP2551SOIC"))
    )
    (comp (ref "U$36")
      (value "MCP2551")
      (footprint "eagle-import:8-SOIC")
      (libsource (lib "eagle-import") (part "MCP2551SOIC"))
    )
    (comp (ref "V1")
      (value "SN74HC08N")
      (footprint "eagle-import:DIL14")
      (libsource (lib "eagle-import") (part "7408N"))
    )
    (comp (ref "V2")
      (value "SN74HC08N")
      (footprint "eagle-import:DIL14")
      (libsource (lib "eagle-import") (part "7408N"))
    )
    (comp (ref "V3")
      (value "SN74HC08N")
      (footprint "eagle-import:DIL14")
      (libsource (lib "eagle-import") (part "7408N"))
    )
  )
  (nets
    (net (code "1") (name "+12V") (class "Default")
      (node (ref "BUZZER") (pin "+") (pinfunction "+_+") (pintype "bidirectional"))
      (node (ref "C19") (pin "+") (pinfunction "+_+") (pintype "passive"))
      (node (ref "C20") (pin "+") (pinfunction "+_+") (pintype "passive"))
      (node (ref "C21") (pin "1") (pinfunction "1_1") (pintype "passive"))
      (node (ref "C22") (pin "1") (pinfunction "1_1") (pintype "passive"))
      (node (ref "FAN1") (pin "1") (pinfunction "S_1") (pintype "passive"))
      (node (ref "FAN2") (pin "1") (pinfunction "S_1") (pintype "passive"))
      (node (ref "FCPRES") (pin "1") (pinfunction "1_1") (pintype "passive"))
      (node (ref "LED1") (pin "A") (pinfunction "A_A") (pintype "passive"))
      (node (ref "POWER") (pin "1") (pinfunction "1_1") (pintype "passive"))
      (node (ref "POWER") (pin "2") (pinfunction "2_2") (pintype "passive"))
      (node (ref "POWER") (pin "3") (pinfunction "3_3") (pintype "passive"))
      (node (ref "POWER") (pin "4") (pinfunction "4_4") (pintype "passive"))
      (node (ref "POWER") (pin "5") (pinfunction "5_5") (pintype "passive"))
      (node (ref "POWER") (pin "6") (pinfunction "6_6") (pintype "passive"))
      (node (ref "R1") (pin "2") (pinfunction "2_2") (pintype "passive"))
      (node (ref "R24") (pin "2") (pinfunction "2_2") (pintype "passive"))
      (node (ref "R33") (pin "2") (pinfunction "2_2") (pintype "passive"))
      (node (ref "R36") (pin "2") (pinfunction "2_2") (pintype "passive"))
      (node (ref "R39") (pin "2") (pinfunction "2_2") (pintype "passive"))
      (node (ref "R42") (pin "2") (pinfunction "2_2") (pintype "passive"))
      (node (ref "R46") (pin "2") (pinfunction "2_2") (pintype "passive"))
      (node (ref "R49") (pin "2") (pinfunction "2_2") (pintype "passive"))
      (node (ref "R52") (pin "2") (pinfunction "2_2") (pintype "passive"))
      (node (ref "R55") (pin "2") (pinfunction "2_2") (pintype "passive"))
      (node (ref "R58") (pin "2") (pinfunction "2_2") (pintype "passive"))
      (node (ref "TANKPRES") (pin "1") (pinfunction "1_1") (pintype "passive"))
      (node (ref "U$10") (pin "C") (pinfunction "C_C") (pintype "passive"))
      (node (ref "U$12") (pin "P$1") (pinfunction "P$2_P$1") (pintype "bidirectional"))
      (node (ref "U$13") (pin "C") (pinfunction "C_C") (pintype "passive"))
      (node (ref "U$15") (pin "P$1") (pinfunction "P$2_P$1") (pintype "bidirectional"))
      (node (ref "U$16") (pin "C") (pinfunction "C_C") (pintype "passive"))
      (node (ref "U$18") (pin "P$1") (pinfunction "P$2_P$1") (pintype "bidirectional"))
      (node (ref "U$19") (pin "C") (pinfunction "C_C") (pintype "passive"))
      (node (ref "U$21") (pin "P$1") (pinfunction "P$2_P$1") (pintype "bidirectional"))
      (node (ref "U$22") (pin "C") (pinfunction "C_C") (pintype "passive"))
      (node (ref "U$24") (pin "P$1") (pinfunction "P$2_P$1") (pintype "bidirectional"))
      (node (ref "U$25") (pin "C") (pinfunction "C_C") (pintype "passive"))
      (node (ref "U$27") (pin "P$1") (pinfunction "P$2_P$1") (pintype "bidirectional"))
      (node (ref "U$28") (pin "C") (pinfunction "C_C") (pintype "passive"))
      (node (ref "U$30") (pin "P$1") (pinfunction "P$2_P$1") (pintype "bidirectional"))
      (node (ref "U$31") (pin "C") (pinfunction "C_C") (pintype "passive"))
      (node (ref "U$33") (pin "P$1") (pinfunction "P$2_P$1") (pintype "bidirectional"))
      (node (ref "U$34") (pin "C") (pinfunction "C_C") (pintype "passive"))
      (node (ref "U$38") (pin "C") (pinfunction "C_C") (pintype "passive"))
      (node (ref "U$6") (pin "P$1") (pinfunction "P$2_P$1") (pintype "bidirectional"))
      (node (ref "U$7") (pin "C") (pinfunction "C_C") (pintype "passive"))
      (node (ref "U$9") (pin "P$1") (pinfunction "P$2_P$1") (pintype "bidirectional"))
    )
    (net (code "2") (name "3V") (class "Default")
      (node (ref "C2") (pin "1") (pinfunction "1_1") (pintype "passive"))
      (node (ref "JP1") (pin "3") (pinfunction "3_3") (pintype "passive"))
      (node (ref "JP3") (pin "3") (pinfunction "3_3") (pintype "passive"))
      (node (ref "LD39300-NNP") (pin "4") (pinfunction "OUT_4") (pintype "passive"))
    )
    (net (code "3") (name "12V_REMOTE_BOTTOM") (class "Default")
      (node (ref "JP4") (pin "2") (pinfunction "2_2") (pintype "passive"))
      (node (ref "U$1") (pin "B_11") (pinfunction "A_B_11") (pintype "passive"))
      (node (ref "U$1") (pin "B_6") (pinfunction "6_B_6") (pintype "bidirectional"))
      (node (ref "U$1") (pin "B_9") (pinfunction "A_B_9") (pintype "passive"))
    )
    (net (code "4") (name "12V_REMOTE_TOP") (class "Default")
      (node (ref "JP4") (pin "1") (pinfunction "1_1") (pintype "passive"))
      (node (ref "U$1") (pin "T_11") (pinfunction "A_T_11") (pintype "passive"))
      (node (ref "U$1") (pin "T_6") (pinfunction "6_T_6") (pintype "bidirectional"))
      (node (ref "U$1") (pin "T_9") (pinfunction "A_T_9") (pintype "passive"))
    )
    (net (code "5") (name "AMBTEMP1") (class "Default")
      (node (ref "R10") (pin "1") (pinfunction "1_1") (pintype "passive"))
      (node (ref "R70") (pin "5") (pinfunction "2_5") (pintype "passive"))
      (node (ref "THERMISTORS") (pin "7") (pinfunction "7_7") (pintype "passive"))
    )
    (net (code "6") (name "AMBTEMP1(S)") (class "Default")
      (node (ref "MCU") (pin "30") (pinfunction "PA22_30") (pintype "bidirectional"))
      (node (ref "R10") (pin "8") (pinfunction "2_8") (pintype "passive"))
      (node (ref "R28") (pin "8") (pinfunction "2_8") (pintype "passive"))
    )
    (net (code "7") (name "AMBTEMP2") (class "Default")
      (node (ref "R10") (pin "2") (pinfunction "1_2") (pintype "passive"))
      (node (ref "R70") (pin "6") (pinfunction "2_6") (pintype "passive"))
      (node (ref "THERMISTORS") (pin "5") (pinfunction "5_5") (pintype "passive"))
    )
    (net (code "8") (name "AMBTEMP2(S)") (class "Default")
      (node (ref "MCU") (pin "31") (pinfunction "PA23_31") (pintype "bidirectional"))
      (node (ref "R10") (pin "7") (pinfunction "2_7") (pintype "passive"))
      (node (ref "R28") (pin "7") (pinfunction "2_7") (pintype "passive"))
    )
    (net (code "9") (name "AMBTEMP3") (class "Default")
      (node (ref "R10") (pin "3") (pinfunction "1_3") (pintype "passive"))
      (node (ref "R70") (pin "7") (pinfunction "2_7") (pintype "passive"))
      (node (ref "THERMISTORS") (pin "3") (pinfunction "3_3") (pintype "passive"))
    )
    (net (code "10") (name "AMBTEMP3(S)") (class "Default")
      (node (ref "MCU") (pin "32") (pinfunction "PA24_32") (pintype "bidirectional"))
      (node (ref "R10") (pin "6") (pinfunction "2_6") (pintype "passive"))
      (node (ref "R28") (pin "6") (pinfunction "2_6") (pintype "passive"))
    )
    (net (code "11") (name "AMBTEMP4") (class "Default")
      (node (ref "R10") (pin "4") (pinfunction "1_4") (pintype "passive"))
      (node (ref "R70") (pin "8") (pinfunction "2_8") (pintype "passive"))
      (node (ref "THERMISTORS") (pin "1") (pinfunction "1_1") (pintype "passive"))
    )
    (net (code "12") (name "AMBTEMP4(S)") (class "Default")
      (node (ref "MCU") (pin "33") (pinfunction "PA25_33") (pintype "bidirectional"))
      (node (ref "R10") (pin "5") (pinfunction "2_5") (pintype "passive"))
      (node (ref "R28") (pin "5") (pinfunction "2_5") (pintype "passive"))
    )
    (net (code "13") (name "ANA_DECOUP") (class "Default")
      (node (ref "C3") (pin "1") (pinfunction "1_1") (pintype "passive"))
      (node (ref "L1") (pin "1") (pinfunction "1_1") (pintype "passive"))
      (node (ref "MCU") (pin "27") (pinfunction "VDDANA_27") (pintype "bidirectional"))
    )
    (net (code "14") (name "BUZZER") (class "Default")
      (node (ref "MCU") (pin "18") (pinfunction "PA12_18") (pintype "bidirectional"))
      (node (ref "R12") (pin "1") (pinfunction "1_1") (pintype "passive"))
    )
    (net (code "15") (name "CAN-EXP_RX") (class "Default")
      (node (ref "MCU") (pin "96") (pinfunction "PB0_96") (pintype "bidirectional"))
      (node (ref "U$36") (pin "4") (pinfunction "RXD_4") (pintype "bidirectional"))
    )
    (net (code "16") (name "CAN-EXP_TX") (class "Default")
      (node (ref "MCU") (pin "97") (pinfunction "PB1_97") (pintype "bidirectional"))
      (node (ref "U$36") (pin "1") (pinfunction "TXD_1") (pintype "bidirectional"))
    )
    (net (code "17") (name "CANEXP_N") (class "Default")
      (node (ref "CAN-EXP") (pin "2") (pinfunction "S_2") (pintype "passive"))
      (node (ref "U$36") (pin "6") (pinfunction "CANL_6") (pintype "bidirectional"))
    )
    (net (code "18") (name "CANEXP_P") (class "Default")
      (node (ref "CAN-EXP") (pin "3") (pinfunction "S_3") (pintype "passive"))
      (node (ref "U$36") (pin "7") (pinfunction "CANH_7") (pintype "bidirectional"))
    )
    (net (code "19") (name "CAN_N") (class "Default")
      (node (ref "U$1") (pin "B_2") (pinfunction "2_B_2") (pintype "bidirectional"))
      (node (ref "U$1") (pin "T_2") (pinfunction "2_T_2") (pintype "bidirectional"))
      (node (ref "U$4") (pin "6") (pinfunction "CANL_6") (pintype "bidirectional"))
    )
    (net (code "20") (name "CAN_P") (class "Default")
      (node (ref "U$1") (pin "B_1") (pinfunction "1_B_1") (pintype "bidirectional"))
      (node (ref "U$1") (pin "T_1") (pinfunction "1_T_1") (pintype "bidirectional"))
      (node (ref "U$4") (pin "7") (pinfunction "CANH_7") (pintype "bidirectional"))
    )
    (net (code "21") (name "CAN_RX") (class "Default")
      (node (ref "MCU") (pin "7") (pinfunction "PB4_7") (pintype "bidirectional"))
      (node (ref "R87") (pin "2") (pinfunction "2_2") (pintype "passive"))
      (node (ref "U$4") (pin "4") (pinfunction "RXD_4") (pintype "bidirectional"))
    )
    (net (code "22") (name "CAN_TX") (class "Default")
      (node (ref "MCU") (pin "8") (pinfunction "PB5_8") (pintype "bidirectional"))
      (node (ref "U$4") (pin "1") (pinfunction "TXD_1") (pintype "bidirectional"))
    )
    (net (code "23") (name "CAPCON(S)") (class "Default")
      (node (ref "CAPCON/VOLT") (pin "2") (pinfunction "2_2") (pintype "passive"))
      (node (ref "MCU") (pin "49") (pinfunction "PC0_49") (pintype "bidirectional"))
      (node (ref "R18") (pin "1") (pinfunction "1_1") (pintype "passive"))
    )
    (net (code "24") (name "CAPCURR") (class "Default")
      (node (ref "CAPCURR") (pin "3") (pinfunction "3_3") (pintype "passive"))
      (node (ref "R74") (pin "2") (pinfunction "2_2") (pintype "passive"))
    )
    (net (code "25") (name "CAPCURR(S)") (class "Default")
      (node (ref "R25") (pin "5") (pinfunction "2_5") (pintype "passive"))
      (node (ref "R73") (pin "2") (pinfunction "2_2") (pintype "passive"))
      (node (ref "R74") (pin "1") (pinfunction "1_1") (pintype "passive"))
    )
    (net (code "26") (name "CAPVOLT") (class "Default")
      (node (ref "R15") (pin "1") (pinfunction "1_1") (pintype "passive"))
      (node (ref "R16") (pin "2") (pinfunction "2_2") (pintype "passive"))
      (node (ref "R25") (pin "7") (pinfunction "2_7") (pintype "passive"))
    )
    (net (code "27") (name "FCCON(S)") (class "Default")
      (node (ref "FCCON/VOLT") (pin "2") (pinfunction "2_2") (pintype "passive"))
      (node (ref "MCU") (pin "46") (pinfunction "PB23_46") (pintype "bidirectional"))
      (node (ref "R17") (pin "1") (pinfunction "1_1") (pintype "passive"))
    )
    (net (code "28") (name "FCCURR") (class "Default")
      (node (ref "FCCURR") (pin "3") (pinfunction "3_3") (pintype "passive"))
      (node (ref "R75") (pin "2") (pinfunction "2_2") (pintype "passive"))
    )
    (net (code "29") (name "FCCURR(S)") (class "Default")
      (node (ref "R25") (pin "6") (pinfunction "2_6") (pintype "passive"))
      (node (ref "R75") (pin "1") (pinfunction "1_1") (pintype "passive"))
      (node (ref "R76") (pin "2") (pinfunction "2_2") (pintype "passive"))
    )
    (net (code "30") (name "FCPRES_S+") (class "Default")
      (node (ref "FCPRES") (pin "2") (pinfunction "2_2") (pintype "passive"))
      (node (ref "R14") (pin "2") (pinfunction "2_2") (pintype "passive"))
      (node (ref "R22") (pin "2") (pinfunction "2_2") (pintype "passive"))
    )
    (net (code "31") (name "FCPRES_S+(S)") (class "Default")
      (node (ref "R13") (pin "2") (pinfunction "2_2") (pintype "passive"))
      (node (ref "R14") (pin "1") (pinfunction "1_1") (pintype "passive"))
      (node (ref "R26") (pin "8") (pinfunction "2_8") (pintype "passive"))
    )
    (net (code "32") (name "FCPRES_S-") (class "Default")
      (node (ref "FCPRES") (pin "3") (pinfunction "3_3") (pintype "passive"))
      (node (ref "R22") (pin "1") (pinfunction "1_1") (pintype "passive"))
      (node (ref "R79") (pin "2") (pinfunction "2_2") (pintype "passive"))
    )
    (net (code "33") (name "FCPRES_S-(S)") (class "Default")
      (node (ref "R26") (pin "7") (pinfunction "2_7") (pintype "passive"))
      (node (ref "R79") (pin "1") (pinfunction "1_1") (pintype "passive"))
      (node (ref "R80") (pin "2") (pinfunction "2_2") (pintype "passive"))
    )
    (net (code "34") (name "FCTEMP1") (class "Default")
      (node (ref "R27") (pin "3") (pinfunction "1_3") (pintype "passive"))
      (node (ref "R9") (pin "7") (pinfunction "2_7") (pintype "passive"))
      (node (ref "THERMISTORS") (pin "11") (pinfunction "11_11") (pintype "passive"))
    )
    (net (code "35") (name "FCTEMP1(S)") (class "Default")
      (node (ref "MCU") (pin "28") (pinfunction "PA20_28") (pintype "bidirectional"))
      (node (ref "R27") (pin "6") (pinfunction "2_6") (pintype "passive"))
      (node (ref "R27") (pin "7") (pinfunction "2_7") (pintype "passive"))
    )
    (net (code "36") (name "FCTEMP2") (class "Default")
      (node (ref "R27") (pin "4") (pinfunction "1_4") (pintype "passive"))
      (node (ref "R9") (pin "8") (pinfunction "2_8") (pintype "passive"))
      (node (ref "THERMISTORS") (pin "9") (pinfunction "9_9") (pintype "passive"))
    )
    (net (code "37") (name "FCTEMP2(S)") (class "Default")
      (node (ref "MCU") (pin "29") (pinfunction "PA21_29") (pintype "bidirectional"))
      (node (ref "R27") (pin "5") (pinfunction "2_5") (pintype "passive"))
      (node (ref "R27") (pin "8") (pinfunction "2_8") (pintype "passive"))
    )
    (net (code "38") (name "FCVOLT") (class "Default")
      (node (ref "R25") (pin "8") (pinfunction "2_8") (pintype "passive"))
      (node (ref "R5") (pin "1") (pinfunction "1_1") (pintype "passive"))
      (node (ref "R6") (pin "2") (pinfunction "2_2") (pintype "passive"))
    )
    (net (code "39") (name "FC_PWR_GOOD") (class "Default")
      (node (ref "MCU") (pin "57") (pinfunction "PC6_57") (pintype "bidirectional"))
      (node (ref "POWER") (pin "13") (pinfunction "13_13") (pintype "passive"))
    )
    (net (code "40") (name "GND") (class "Default")
      (node (ref "4-NMOS") (pin "12") (pinfunction "12_12") (pintype "passive"))
      (node (ref "4-NMOS") (pin "3") (pinfunction "3_3") (pintype "passive"))
      (node (ref "4-NMOS") (pin "4") (pinfunction "4_4") (pintype "passive"))
      (node (ref "4-NMOS") (pin "7") (pinfunction "7_7") (pintype "passive"))
      (node (ref "4-NMOS") (pin "8") (pinfunction "8_8") (pintype "passive"))
      (node (ref "4-NMOS1") (pin "12") (pinfunction "12_12") (pintype "passive"))
      (node (ref "4-NMOS1") (pin "3") (pinfunction "3_3") (pintype "passive"))
      (node (ref "4-NMOS1") (pin "4") (pinfunction "4_4") (pintype "passive"))
      (node (ref "4-NMOS1") (pin "7") (pinfunction "7_7") (pintype "passive"))
      (node (ref "4-NMOS1") (pin "8") (pinfunction "8_8") (pintype "passive"))
      (node (ref "C1") (pin "2") (pinfunction "2_2") (pintype "passive"))
      (node (ref "C10") (pin "1") (pinfunction "1_1") (pintype "passive"))
      (node (ref "C11") (pin "-") (pinfunction "-_-") (pintype "passive"))
      (node (ref "C13") (pin "2") (pinfunction "2_2") (pintype "passive"))
      (node (ref "C14") (pin "2") (pinfunction "2_2") (pintype "passive"))
      (node (ref "C15") (pin "-") (pinfunction "-_-") (pintype "passive"))
      (node (ref "C16") (pin "2") (pinfunction "2_2") (pintype "passive"))
      (node (ref "C17") (pin "2") (pinfunction "2_2") (pintype "passive"))
      (node (ref "C18") (pin "2") (pinfunction "2_2") (pintype "passive"))
      (node (ref "C19") (pin "-") (pinfunction "-_-") (pintype "passive"))
      (node (ref "C2") (pin "2") (pinfunction "2_2") (pintype "passive"))
      (node (ref "C20") (pin "-") (pinfunction "-_-") (pintype "passive"))
      (node (ref "C21") (pin "2") (pinfunction "2_2") (pintype "passive"))
      (node (ref "C22") (pin "2") (pinfunction "2_2") (pintype "passive"))
      (node (ref "C23") (pin "2") (pinfunction "2_2") (pintype "passive"))
      (node (ref "C24") (pin "2") (pinfunction "2_2") (pintype "passive"))
      (node (ref "C25") (pin "2") (pinfunction "2_2") (pintype "passive"))
      (node (ref "C3") (pin "2") (pinfunction "2_2") (pintype "passive"))
      (node (ref "C4") (pin "2") (pinfunction "2_2") (pintype "passive"))
      (node (ref "C5") (pin "2") (pinfunction "2_2") (pintype "passive"))
      (node (ref "C6") (pin "2") (pinfunction "2_2") (pintype "passive"))
      (node (ref "C7") (pin "2") (pinfunction "2_2") (pintype "passive"))
      (node (ref "C8") (pin "2") (pinfunction "2_2") (pintype "passive"))
      (node (ref "C9") (pin "2") (pinfunction "2_2") (pintype "passive"))
      (node (ref "CAN-EXP") (pin "4") (pinfunction "S_4") (pintype "passive"))
      (node (ref "CAPCURR") (pin "2") (pinfunction "2_2") (pintype "passive"))
      (node (ref "EXT-LEDS") (pin "2") (pinfunction "S_2") (pintype "passive"))
      (node (ref "FAN1") (pin "4") (pinfunction "S_4") (pintype "passive"))
      (node (ref "FAN2") (pin "4") (pinfunction "S_4") (pintype "passive"))
      (node (ref "FCCURR") (pin "2") (pinfunction "2_2") (pintype "passive"))
      (node (ref "FCPRES") (pin "4") (pinfunction "4_4") (pintype "passive"))
      (node (ref "JP2") (pin "GND") (pinfunction "GND_GND") (pintype "bidirectional"))
      (node (ref "JP2") (pin "MT1") (pinfunction "GND_MT1") (pintype "bidirectional"))
      (node (ref "JP2") (pin "MT2") (pinfunction "GND_MT2") (pintype "bidirectional"))
      (node (ref "JTAG") (pin "10") (pinfunction "10_10") (pintype "passive"))
      (node (ref "JTAG") (pin "2") (pinfunction "2_2") (pintype "passive"))
      (node (ref "LD39300-NNP") (pin "1") (pinfunction "ADJ_1") (pintype "input"))
      (node (ref "MCU") (pin "26") (pinfunction "GNDANA_26") (pintype "bidirectional"))
      (node (ref "MCU") (pin "37") (pinfunction "GNDPLL_37") (pintype "bidirectional"))
      (node (ref "MCU") (pin "41") (pinfunction "GNDCORE_41") (pintype "bidirectional"))
      (node (ref "MCU") (pin "54") (pinfunction "GNDIO2_54") (pintype "bidirectional"))
      (node (ref "MCU") (pin "6") (pinfunction "GNDIO1_6") (pintype "bidirectional"))
      (node (ref "MCU") (pin "83") (pinfunction "GNDIO3_83") (pintype "bidirectional"))
      (node (ref "POWER") (pin "10") (pinfunction "10_10") (pintype "passive"))
      (node (ref "POWER") (pin "11") (pinfunction "11_11") (pintype "passive"))
      (node (ref "POWER") (pin "12") (pinfunction "12_12") (pintype "passive"))
      (node (ref "POWER") (pin "14") (pinfunction "14_14") (pintype "passive"))
      (node (ref "POWER") (pin "7") (pinfunction "7_7") (pintype "passive"))
      (node (ref "POWER") (pin "8") (pinfunction "8_8") (pintype "passive"))
      (node (ref "POWER") (pin "9") (pinfunction "9_9") (pintype "passive"))
      (node (ref "PWR_12") (pin "C") (pinfunction "C_C") (pintype "passive"))
      (node (ref "R11") (pin "1") (pinfunction "1_1") (pintype "passive"))
      (node (ref "R13") (pin "1") (pinfunction "1_1") (pintype "passive"))
      (node (ref "R15") (pin "2") (pinfunction "2_2") (pintype "passive"))
      (node (ref "R17") (pin "2") (pinfunction "2_2") (pintype "passive"))
      (node (ref "R18") (pin "2") (pinfunction "2_2") (pintype "passive"))
      (node (ref "R19") (pin "2") (pinfunction "2_2") (pintype "passive"))
      (node (ref "R2") (pin "1") (pinfunction "1_1") (pintype "passive"))
      (node (ref "R20") (pin "2") (pinfunction "2_2") (pintype "passive"))
      (node (ref "R27") (pin "1") (pinfunction "1_1") (pintype "passive"))
      (node (ref "R27") (pin "2") (pinfunction "1_2") (pintype "passive"))
      (node (ref "R28") (pin "1") (pinfunction "1_1") (pintype "passive"))
      (node (ref "R28") (pin "2") (pinfunction "1_2") (pintype "passive"))
      (node (ref "R28") (pin "3") (pinfunction "1_3") (pintype "passive"))
      (node (ref "R28") (pin "4") (pinfunction "1_4") (pintype "passive"))
      (node (ref "R32") (pin "1") (pinfunction "1_1") (pintype "passive"))
      (node (ref "R35") (pin "1") (pinfunction "1_1") (pintype "passive"))
      (node (ref "R38") (pin "1") (pinfunction "1_1") (pintype "passive"))
      (node (ref "R4") (pin "2") (pinfunction "2_2") (pintype "passive"))
      (node (ref "R41") (pin "1") (pinfunction "1_1") (pintype "passive"))
      (node (ref "R44") (pin "1") (pinfunction "1_1") (pintype "passive"))
      (node (ref "R48") (pin "1") (pinfunction "1_1") (pintype "passive"))
      (node (ref "R5") (pin "2") (pinfunction "2_2") (pintype "passive"))
      (node (ref "R51") (pin "1") (pinfunction "1_1") (pintype "passive"))
      (node (ref "R54") (pin "1") (pinfunction "1_1") (pintype "passive"))
      (node (ref "R57") (pin "1") (pinfunction "1_1") (pintype "passive"))
      (node (ref "R59") (pin "2") (pinfunction "2_2") (pintype "passive"))
      (node (ref "R60") (pin "2") (pinfunction "2_2") (pintype "passive"))
      (node (ref "R61") (pin "2") (pinfunction "2_2") (pintype "passive"))
      (node (ref "R62") (pin "2") (pinfunction "2_2") (pintype "passive"))
      (node (ref "R63") (pin "2") (pinfunction "2_2") (pintype "passive"))
      (node (ref "R68") (pin "5") (pinfunction "2_5") (pintype "passive"))
      (node (ref "R68") (pin "6") (pinfunction "2_6") (pintype "passive"))
      (node (ref "R68") (pin "7") (pinfunction "2_7") (pintype "passive"))
      (node (ref "R68") (pin "8") (pinfunction "2_8") (pintype "passive"))
      (node (ref "R69") (pin "1") (pinfunction "1_1") (pintype "passive"))
      (node (ref "R72") (pin "1") (pinfunction "1_1") (pintype "passive"))
      (node (ref "R73") (pin "1") (pinfunction "1_1") (pintype "passive"))
      (node (ref "R76") (pin "1") (pinfunction "1_1") (pintype "passive"))
      (node (ref "R78") (pin "1") (pinfunction "1_1") (pintype "passive"))
      (node (ref "R8") (pin "1") (pinfunction "1_1") (pintype "passive"))
      (node (ref "R80") (pin "1") (pinfunction "1_1") (pintype "passive"))
      (node (ref "R82") (pin "1") (pinfunction "1_1") (pintype "passive"))
      (node (ref "R88") (pin "2") (pinfunction "2_2") (pintype "passive"))
      (node (ref "RESET") (pin "1") (pinfunction "1_1") (pintype "passive"))
      (node (ref "SERVO1") (pin "1") (pinfunction "S_1") (pintype "passive"))
      (node (ref "SERVO2") (pin "1") (pinfunction "S_1") (pintype "passive"))
      (node (ref "SYS_OK") (pin "P$2") (pinfunction "P$1_P$2") (pintype "bidirectional"))
      (node (ref "TANKPRES") (pin "4") (pinfunction "4_4") (pintype "passive"))
      (node (ref "THERMISTORS") (pin "10") (pinfunction "10_10") (pintype "passive"))
      (node (ref "THERMISTORS") (pin "12") (pinfunction "12_12") (pintype "passive"))
      (node (ref "THERMISTORS") (pin "14") (pinfunction "14_14") (pintype "passive"))
      (node (ref "THERMISTORS") (pin "2") (pinfunction "2_2") (pintype "passive"))
      (node (ref "THERMISTORS") (pin "4") (pinfunction "4_4") (pintype "passive"))
      (node (ref "THERMISTORS") (pin "6") (pinfunction "6_6") (pintype "passive"))
      (node (ref "THERMISTORS") (pin "8") (pinfunction "8_8") (pintype "passive"))
      (node (ref "U$1") (pin "B_8") (pinfunction "8_B_8") (pintype "bidirectional"))
      (node (ref "U$1") (pin "T_8") (pinfunction "8_T_8") (pintype "bidirectional"))
      (node (ref "U$11") (pin "S@0") (pinfunction "S_S@0") (pintype "passive"))
      (node (ref "U$11") (pin "S@1") (pinfunction "S_S@1") (pintype "passive"))
      (node (ref "U$14") (pin "S@0") (pinfunction "S_S@0") (pintype "passive"))
      (node (ref "U$14") (pin "S@1") (pinfunction "S_S@1") (pintype "passive"))
      (node (ref "U$17") (pin "S@0") (pinfunction "S_S@0") (pintype "passive"))
      (node (ref "U$17") (pin "S@1") (pinfunction "S_S@1") (pintype "passive"))
      (node (ref "U$2") (pin "10") (pinfunction "P$1_10") (pintype "bidirectional"))
      (node (ref "U$20") (pin "S@0") (pinfunction "S_S@0") (pintype "passive"))
      (node (ref "U$20") (pin "S@1") (pinfunction "S_S@1") (pintype "passive"))
      (node (ref "U$23") (pin "S@0") (pinfunction "S_S@0") (pintype "passive"))
      (node (ref "U$23") (pin "S@1") (pinfunction "S_S@1") (pintype "passive"))
      (node (ref "U$26") (pin "S@0") (pinfunction "S_S@0") (pintype "passive"))
      (node (ref "U$26") (pin "S@1") (pinfunction "S_S@1") (pintype "passive"))
      (node (ref "U$29") (pin "S@0") (pinfunction "S_S@0") (pintype "passive"))
      (node (ref "U$29") (pin "S@1") (pinfunction "S_S@1") (pintype "passive"))
      (node (ref "U$3") (pin "1") (pinfunction "P$1_1") (pintype "bidirectional"))
      (node (ref "U$32") (pin "S@0") (pinfunction "S_S@0") (pintype "passive"))
      (node (ref "U$32") (pin "S@1") (pinfunction "S_S@1") (pintype "passive"))
      (node (ref "U$35") (pin "S@0") (pinfunction "S_S@0") (pintype "passive"))
      (node (ref "U$35") (pin "S@1") (pinfunction "S_S@1") (pintype "passive"))
      (node (ref "U$36") (pin "2") (pinfunction "VSS/GND_2") (pintype "bidirectional"))
      (node (ref "U$36") (pin "8") (pinfunction "RS_8") (pintype "bidirectional"))
      (node (ref "U$37") (pin "S@0") (pinfunction "S_S@0") (pintype "passive"))
      (node (ref "U$37") (pin "S@1") (pinfunction "S_S@1") (pintype "passive"))
      (node (ref "U$39") (pin "S@0") (pinfunction "S_S@0") (pintype "passive"))
      (node (ref "U$39") (pin "S@1") (pinfunction "S_S@1") (pintype "passive"))
      (node (ref "U$4") (pin "2") (pinfunction "VSS/GND_2") (pintype "bidirectional"))
      (node (ref "U$4") (pin "8") (pinfunction "RS_8") (pintype "bidirectional"))
      (node (ref "U$5") (pin "S@0") (pinfunction "S_S@0") (pintype "passive"))
      (node (ref "U$5") (pin "S@1") (pinfunction "S_S@1") (pintype "passive"))
      (node (ref "U$8") (pin "S@0") (pinfunction "S_S@0") (pintype "passive"))
      (node (ref "U$8") (pin "S@1") (pinfunction "S_S@1") (pintype "passive"))
    )
    (net (code "41") (name "LED0") (class "Default")
      (node (ref "4-NMOS") (pin "6") (pinfunction "6_6") (pintype "passive"))
      (node (ref "MCU") (pin "44") (pinfunction "PB21_44") (pintype "bidirectional"))
    )
    (net (code "42") (name "LED0_O") (class "Default")
      (node (ref "D0") (pin "C") (pinfunction "C_C") (pintype "passive"))
      (node (ref "EXT-LEDS") (pin "3") (pinfunction "S_3") (pintype "passive"))
      (node (ref "R30") (pin "5") (pinfunction "2_5") (pintype "passive"))
    )
    (net (code "43") (name "LED1") (class "Default")
      (node (ref "4-NMOS") (pin "2") (pinfunction "2_2") (pintype "passive"))
      (node (ref "MCU") (pin "47") (pinfunction "PB30_47") (pintype "bidirectional"))
    )
    (net (code "44") (name "LED1_O") (class "Default")
      (node (ref "D1") (pin "C") (pinfunction "C_C") (pintype "passive"))
      (node (ref "EXT-LEDS") (pin "4") (pinfunction "S_4") (pintype "passive"))
      (node (ref "R30") (pin "6") (pinfunction "2_6") (pintype "passive"))
    )
    (net (code "45") (name "LED2") (class "Default")
      (node (ref "4-NMOS") (pin "13") (pinfunction "13_13") (pintype "passive"))
      (node (ref "MCU") (pin "42") (pinfunction "PB19_42") (pintype "bidirectional"))
    )
    (net (code "46") (name "LED2_O") (class "Default")
      (node (ref "D2") (pin "C") (pinfunction "C_C") (pintype "passive"))
      (node (ref "EXT-LEDS") (pin "5") (pinfunction "S_5") (pintype "passive"))
      (node (ref "R30") (pin "7") (pinfunction "2_7") (pintype "passive"))
    )
    (net (code "47") (name "LED3") (class "Default")
      (node (ref "4-NMOS") (pin "9") (pinfunction "9_9") (pintype "passive"))
      (node (ref "MCU") (pin "43") (pinfunction "PB20_43") (pintype "bidirectional"))
    )
    (net (code "48") (name "LED3_O") (class "Default")
      (node (ref "D3") (pin "C") (pinfunction "C_C") (pintype "passive"))
      (node (ref "EXT-LEDS") (pin "6") (pinfunction "S_6") (pintype "passive"))
      (node (ref "R30") (pin "8") (pinfunction "2_8") (pintype "passive"))
    )
    (net (code "49") (name "LED_ERROR") (class "Default")
      (node (ref "4-NMOS1") (pin "9") (pinfunction "9_9") (pintype "passive"))
      (node (ref "MCU") (pin "51") (pinfunction "PC2_51") (pintype "bidirectional"))
    )
    (net (code "50") (name "LED_RUN") (class "Default")
      (node (ref "4-NMOS1") (pin "2") (pinfunction "2_2") (pintype "passive"))
      (node (ref "MCU") (pin "48") (pinfunction "PB31_48") (pintype "bidirectional"))
    )
    (net (code "51") (name "LED_START") (class "Default")
      (node (ref "4-NMOS1") (pin "6") (pinfunction "6_6") (pintype "passive"))
      (node (ref "MCU") (pin "50") (pinfunction "PC1_50") (pintype "bidirectional"))
    )
    (net (code "52") (name "LED_STOP") (class "Default")
      (node (ref "4-NMOS1") (pin "13") (pinfunction "13_13") (pintype "passive"))
      (node (ref "MCU") (pin "52") (pinfunction "PC3_52") (pintype "bidirectional"))
    )
    (net (code "53") (name "MCU_RST") (class "Default")
      (node (ref "C10") (pin "2") (pinfunction "2_2") (pintype "passive"))
      (node (ref "JTAG") (pin "6") (pinfunction "6_6") (pintype "passive"))
      (node (ref "MCU") (pin "98") (pinfunction "~{RESET}_98") (pintype "bidirectional"))
      (node (ref "R23") (pin "1") (pinfunction "1_1") (pintype "passive"))
      (node (ref "RESET") (pin "3") (pinfunction "2_3") (pintype "passive"))
    )
    (net (code "54") (name "MFLOW") (class "Default")
      (node (ref "R81") (pin "2") (pinfunction "2_2") (pintype "passive"))
      (node (ref "THERMISTORS") (pin "13") (pinfunction "13_13") (pintype "passive"))
    )
    (net (code "55") (name "MFLOW(S)") (class "Default")
      (node (ref "MCU") (pin "25") (pinfunction "PA19_25") (pintype "bidirectional"))
      (node (ref "R81") (pin "1") (pinfunction "1_1") (pintype "passive"))
      (node (ref "R82") (pin "2") (pinfunction "2_2") (pintype "passive"))
    )
    (net (code "56") (name "N$10") (class "Default")
      (node (ref "C12") (pin "1") (pinfunction "1_1") (pintype "passive"))
      (node (ref "MCU") (pin "23") (pinfunction "ADCREFP_23") (pintype "bidirectional"))
    )
    (net (code "57") (name "N$11") (class "Default")
      (node (ref "C12") (pin "2") (pinfunction "2_2") (pintype "passive"))
      (node (ref "MCU") (pin "24") (pinfunction "ADCREFN_24") (pintype "bidirectional"))
    )
    (net (code "58") (name "N$91") (class "Default")
      (node (ref "JTAG") (pin "8") (pinfunction "8_8") (pintype "passive"))
      (node (ref "R45") (pin "1") (pinfunction "1_1") (pintype "passive"))
    )
    (net (code "59") (name "Net-(4-NMOS-Pad10)") (class "Default")
      (node (ref "4-NMOS") (pin "10") (pinfunction "10_10") (pintype "passive"))
      (node (ref "R30") (pin "1") (pinfunction "1_1") (pintype "passive"))
    )
    (net (code "60") (name "Net-(4-NMOS1-Pad10)") (class "Default")
      (node (ref "4-NMOS1") (pin "10") (pinfunction "10_10") (pintype "passive"))
      (node (ref "R7") (pin "1") (pinfunction "1_1") (pintype "passive"))
    )
    (net (code "61") (name "Net-(BUZZER-Pad-)") (class "Default")
      (node (ref "BUZZER") (pin "-") (pinfunction "-_-") (pintype "bidirectional"))
      (node (ref "U$37") (pin "D") (pinfunction "D_D") (pintype "passive"))
      (node (ref "U$38") (pin "A") (pinfunction "A_A") (pintype "passive"))
    )
    (net (code "62") (name "Net-(C24-Pad1)") (class "Default")
      (node (ref "C24") (pin "1") (pinfunction "1_1") (pintype "passive"))
      (node (ref "CAPCURR") (pin "1") (pinfunction "1_1") (pintype "passive"))
      (node (ref "JP1") (pin "2") (pinfunction "2_2") (pintype "passive"))
    )
    (net (code "63") (name "Net-(C25-Pad1)") (class "Default")
      (node (ref "C25") (pin "1") (pinfunction "1_1") (pintype "passive"))
      (node (ref "FCCURR") (pin "1") (pinfunction "1_1") (pintype "passive"))
      (node (ref "JP3") (pin "2") (pinfunction "2_2") (pintype "passive"))
    )
    (net (code "64") (name "Net-(CAPCON/VOLT-Pad1)") (class "Default")
      (node (ref "CAPCON/VOLT") (pin "1") (pinfunction "1_1") (pintype "passive"))
      (node (ref "R16") (pin "1") (pinfunction "1_1") (pintype "passive"))
    )
    (net (code "65") (name "Net-(FAN1B-S)") (class "Default")
      (node (ref "FAN1") (pin "2") (pinfunction "S_2") (pintype "passive"))
      (node (ref "FAN2") (pin "2") (pinfunction "S_2") (pintype "passive"))
      (node (ref "R64") (pin "2") (pinfunction "2_2") (pintype "passive"))
    )
    (net (code "66") (name "Net-(FCCON/VOLT-Pad1)") (class "Default")
      (node (ref "FCCON/VOLT") (pin "1") (pinfunction "1_1") (pintype "passive"))
      (node (ref "R6") (pin "1") (pinfunction "1_1") (pintype "passive"))
    )
    (net (code "67") (name "Net-(LED1-PadC)") (class "Default")
      (node (ref "LED1") (pin "C") (pinfunction "C_C") (pintype "passive"))
      (node (ref "R66") (pin "1") (pinfunction "1_1") (pintype "passive"))
    )
    (net (code "68") (name "Net-(LED6-PadA)") (class "Default")
      (node (ref "LED6") (pin "A") (pinfunction "A_A") (pintype "passive"))
      (node (ref "R24") (pin "1") (pinfunction "1_1") (pintype "passive"))
    )
    (net (code "69") (name "Net-(LED7-PadA)") (class "Default")
      (node (ref "LED7") (pin "A") (pinfunction "A_A") (pintype "passive"))
      (node (ref "R33") (pin "1") (pinfunction "1_1") (pintype "passive"))
    )
    (net (code "70") (name "Net-(LED8-PadA)") (class "Default")
      (node (ref "LED8") (pin "A") (pinfunction "A_A") (pintype "passive"))
      (node (ref "R36") (pin "1") (pinfunction "1_1") (pintype "passive"))
    )
    (net (code "71") (name "Net-(LED9-PadA)") (class "Default")
      (node (ref "LED9") (pin "A") (pinfunction "A_A") (pintype "passive"))
      (node (ref "R39") (pin "1") (pinfunction "1_1") (pintype "passive"))
    )
    (net (code "72") (name "Net-(LED10-PadA)") (class "Default")
      (node (ref "LED10") (pin "A") (pinfunction "A_A") (pintype "passive"))
      (node (ref "R42") (pin "1") (pinfunction "1_1") (pintype "passive"))
    )
    (net (code "73") (name "Net-(LED11-PadA)") (class "Default")
      (node (ref "LED11") (pin "A") (pinfunction "A_A") (pintype "passive"))
      (node (ref "R46") (pin "1") (pinfunction "1_1") (pintype "passive"))
    )
    (net (code "74") (name "Net-(LED12-PadA)") (class "Default")
      (node (ref "LED12") (pin "A") (pinfunction "A_A") (pintype "passive"))
      (node (ref "R49") (pin "1") (pinfunction "1_1") (pintype "passive"))
    )
    (net (code "75") (name "Net-(LED13-PadA)") (class "Default")
      (node (ref "LED13") (pin "A") (pinfunction "A_A") (pintype "passive"))
      (node (ref "R52") (pin "1") (pinfunction "1_1") (pintype "passive"))
    )
    (net (code "76") (name "Net-(LED14-PadA)") (class "Default")
      (node (ref "LED14") (pin "A") (pinfunction "A_A") (pintype "passive"))
      (node (ref "R55") (pin "1") (pinfunction "1_1") (pintype "passive"))
    )
    (net (code "77") (name "Net-(LED15-PadA)") (class "Default")
      (node (ref "LED15") (pin "A") (pinfunction "A_A") (pintype "passive"))
      (node (ref "R58") (pin "1") (pinfunction "1_1") (pintype "passive"))
    )
    (net (code "78") (name "Net-(MCU-PA4)") (class "Default")
      (node (ref "MCU") (pin "10") (pinfunction "PA4_10") (pintype "bidirectional"))
      (node (ref "R29") (pin "2") (pinfunction "2_2") (pintype "passive"))
    )
    (net (code "79") (name "Net-(MCU-PA5)") (class "Default")
      (node (ref "MCU") (pin "11") (pinfunction "PA5_11") (pintype "bidirectional"))
      (node (ref "R26") (pin "3") (pinfunction "1_3") (pintype "passive"))
    )
    (net (code "80") (name "Net-(MCU-PA6)") (class "Default")
      (node (ref "MCU") (pin "12") (pinfunction "PA6_12") (pintype "bidirectional"))
      (node (ref "R26") (pin "2") (pinfunction "1_2") (pintype "passive"))
    )
    (net (code "81") (name "Net-(MCU-PA7)") (class "Default")
      (node (ref "MCU") (pin "13") (pinfunction "PA7_13") (pintype "bidirectional"))
      (node (ref "R26") (pin "1") (pinfunction "1_1") (pintype "passive"))
    )
    (net (code "82") (name "Net-(MCU-PA8)") (class "Default")
      (node (ref "MCU") (pin "14") (pinfunction "PA8_14") (pintype "bidirectional"))
      (node (ref "R25") (pin "4") (pinfunction "1_4") (pintype "passive"))
    )
    (net (code "83") (name "Net-(MCU-PA9)") (class "Default")
      (node (ref "MCU") (pin "15") (pinfunction "PA9_15") (pintype "bidirectional"))
      (node (ref "R25") (pin "3") (pinfunction "1_3") (pintype "passive"))
    )
    (net (code "84") (name "Net-(MCU-PA10)") (class "Default")
      (node (ref "MCU") (pin "16") (pinfunction "PA10_16") (pintype "bidirectional"))
      (node (ref "R25") (pin "2") (pinfunction "1_2") (pintype "passive"))
    )
    (net (code "85") (name "Net-(MCU-PA11)") (class "Default")
      (node (ref "MCU") (pin "17") (pinfunction "PA11_17") (pintype "bidirectional"))
      (node (ref "R25") (pin "1") (pinfunction "1_1") (pintype "passive"))
    )
    (net (code "86") (name "Net-(MCU-PC7)") (class "Default")
      (node (ref "MCU") (pin "58") (pinfunction "PC7_58") (pintype "bidirectional"))
      (node (ref "U$2") (pin "8") (pinfunction "P$1_8") (pintype "bidirectional"))
    )
    (net (code "87") (name "Net-(MCU-PC12)") (class "Default")
      (node (ref "MCU") (pin "60") (pinfunction "PC12_60") (pintype "bidirectional"))
      (node (ref "U$2") (pin "7") (pinfunction "P$1_7") (pintype "bidirectional"))
    )
    (net (code "88") (name "Net-(MCU-PC14)") (class "Default")
      (node (ref "MCU") (pin "62") (pinfunction "PC14_62") (pintype "bidirectional"))
      (node (ref "U$2") (pin "6") (pinfunction "P$1_6") (pintype "bidirectional"))
    )
    (net (code "89") (name "Net-(MCU-PC15)") (class "Default")
      (node (ref "MCU") (pin "63") (pinfunction "PC15_63") (pintype "bidirectional"))
      (node (ref "U$3") (pin "5") (pinfunction "P$1_5") (pintype "bidirectional"))
    )
    (net (code "90") (name "Net-(MCU-PC16)") (class "Default")
      (node (ref "MCU") (pin "64") (pinfunction "PC16_64") (pintype "bidirectional"))
      (node (ref "U$2") (pin "5") (pinfunction "P$1_5") (pintype "bidirectional"))
    )
    (net (code "91") (name "Net-(MCU-PC17)") (class "Default")
      (node (ref "MCU") (pin "65") (pinfunction "PC17_65") (pintype "bidirectional"))
      (node (ref "U$3") (pin "6") (pinfunction "P$1_6") (pintype "bidirectional"))
    )
    (net (code "92") (name "Net-(MCU-PC18)") (class "Default")
      (node (ref "MCU") (pin "66") (pinfunction "PC18_66") (pintype "bidirectional"))
      (node (ref "U$2") (pin "4") (pinfunction "P$1_4") (pintype "bidirectional"))
    )
    (net (code "93") (name "Net-(MCU-PC19)") (class "Default")
      (node (ref "MCU") (pin "67") (pinfunction "PC19_67") (pintype "bidirectional"))
      (node (ref "U$3") (pin "7") (pinfunction "P$1_7") (pintype "bidirectional"))
    )
    (net (code "94") (name "Net-(MCU-PC20)") (class "Default")
      (node (ref "MCU") (pin "68") (pinfunction "PC20_68") (pintype "bidirectional"))
      (node (ref "U$2") (pin "3") (pinfunction "P$1_3") (pintype "bidirectional"))
    )
    (net (code "95") (name "Net-(MCU-PC21)") (class "Default")
      (node (ref "MCU") (pin "69") (pinfunction "PC21_69") (pintype "bidirectional"))
      (node (ref "U$3") (pin "8") (pinfunction "P$1_8") (pintype "bidirectional"))
    )
    (net (code "96") (name "Net-(MCU-PC22)") (class "Default")
      (node (ref "MCU") (pin "70") (pinfunction "PC22_70") (pintype "bidirectional"))
      (node (ref "U$2") (pin "2") (pinfunction "P$1_2") (pintype "bidirectional"))
    )
    (net (code "97") (name "Net-(MCU-PC23)") (class "Default")
      (node (ref "MCU") (pin "71") (pinfunction "PC23_71") (pintype "bidirectional"))
      (node (ref "U$3") (pin "9") (pinfunction "P$1_9") (pintype "bidirectional"))
    )
    (net (code "98") (name "Net-(MCU-PC24)") (class "Default")
      (node (ref "MCU") (pin "72") (pinfunction "PC24_72") (pintype "bidirectional"))
      (node (ref "U$2") (pin "1") (pinfunction "P$1_1") (pintype "bidirectional"))
    )
    (net (code "99") (name "Net-(MCU-PC31)") (class "Default")
      (node (ref "MCU") (pin "73") (pinfunction "PC31_73") (pintype "bidirectional"))
      (node (ref "U$3") (pin "10") (pinfunction "P$1_10") (pintype "bidirectional"))
    )
    (net (code "100") (name "Net-(MCU-VDDCORE)") (class "Default")
      (node (ref "C16") (pin "1") (pinfunction "1_1") (pintype "passive"))
      (node (ref "C8") (pin "1") (pinfunction "1_1") (pintype "passive"))
      (node (ref "C9") (pin "1") (pinfunction "1_1") (pintype "passive"))
      (node (ref "MCU") (pin "40") (pinfunction "VDDCORE_40") (pintype "bidirectional"))
    )
    (net (code "101") (name "Net-(MCU-VDD_33)") (class "Default")
      (node (ref "C14") (pin "1") (pinfunction "1_1") (pintype "passive"))
      (node (ref "C6") (pin "1") (pinfunction "1_1") (pintype "passive"))
      (node (ref "C7") (pin "1") (pinfunction "1_1") (pintype "passive"))
      (node (ref "MCU") (pin "39") (pinfunction "VDD_33_39") (pintype "bidirectional"))
    )
    (net (code "102") (name "Net-(PWR_12-PadA)") (class "Default")
      (node (ref "PWR_12") (pin "A") (pinfunction "A_A") (pintype "passive"))
      (node (ref "R1") (pin "1") (pinfunction "1_1") (pintype "passive"))
    )
    (net (code "103") (name "Net-(R3-Pad2)") (class "Default")
      (node (ref "R3") (pin "2") (pinfunction "2_2") (pintype "passive"))
      (node (ref "R8") (pin "2") (pinfunction "2_2") (pintype "passive"))
      (node (ref "U$5") (pin "G") (pinfunction "G_G") (pintype "passive"))
    )
    (net (code "104") (name "Net-(R7A-2)") (class "Default")
      (node (ref "LERROR") (pin "C") (pinfunction "C_C") (pintype "passive"))
      (node (ref "R7") (pin "8") (pinfunction "2_8") (pintype "passive"))
    )
    (net (code "105") (name "Net-(R7B-1)") (class "Default")
      (node (ref "4-NMOS1") (pin "14") (pinfunction "14_14") (pintype "passive"))
      (node (ref "R7") (pin "2") (pinfunction "1_2") (pintype "passive"))
    )
    (net (code "106") (name "Net-(R7B-2)") (class "Default")
      (node (ref "LSTOP") (pin "C") (pinfunction "C_C") (pintype "passive"))
      (node (ref "R7") (pin "7") (pinfunction "2_7") (pintype "passive"))
    )
    (net (code "107") (name "Net-(R7C-1)") (class "Default")
      (node (ref "4-NMOS1") (pin "5") (pinfunction "5_5") (pintype "passive"))
      (node (ref "R7") (pin "4") (pinfunction "1_4") (pintype "passive"))
    )
    (net (code "108") (name "Net-(R7C-2)") (class "Default")
      (node (ref "LSTART") (pin "C") (pinfunction "C_C") (pintype "passive"))
      (node (ref "R7") (pin "5") (pinfunction "2_5") (pintype "passive"))
    )
    (net (code "109") (name "Net-(R7D-1)") (class "Default")
      (node (ref "4-NMOS1") (pin "1") (pinfunction "1_1") (pintype "passive"))
      (node (ref "R7") (pin "3") (pinfunction "1_3") (pintype "passive"))
    )
    (net (code "110") (name "Net-(R7D-2)") (class "Default")
      (node (ref "LRUN") (pin "C") (pinfunction "C_C") (pintype "passive"))
      (node (ref "R7") (pin "6") (pinfunction "2_6") (pintype "passive"))
    )
    (net (code "111") (name "Net-(R11-Pad2)") (class "Default")
      (node (ref "R11") (pin "2") (pinfunction "2_2") (pintype "passive"))
      (node (ref "R12") (pin "2") (pinfunction "2_2") (pintype "passive"))
      (node (ref "U$37") (pin "G") (pinfunction "G_G") (pintype "passive"))
    )
    (net (code "112") (name "Net-(R30B-1)") (class "Default")
      (node (ref "4-NMOS") (pin "14") (pinfunction "14_14") (pintype "passive"))
      (node (ref "R30") (pin "2") (pinfunction "1_2") (pintype "passive"))
    )
    (net (code "113") (name "Net-(R30C-1)") (class "Default")
      (node (ref "4-NMOS") (pin "5") (pinfunction "5_5") (pintype "passive"))
      (node (ref "R30") (pin "4") (pinfunction "1_4") (pintype "passive"))
    )
    (net (code "114") (name "Net-(R30D-1)") (class "Default")
      (node (ref "4-NMOS") (pin "1") (pinfunction "1_1") (pintype "passive"))
      (node (ref "R30") (pin "3") (pinfunction "1_3") (pintype "passive"))
    )
    (net (code "115") (name "Net-(R31-Pad2)") (class "Default")
      (node (ref "R31") (pin "2") (pinfunction "2_2") (pintype "passive"))
      (node (ref "R32") (pin "2") (pinfunction "2_2") (pintype "passive"))
      (node (ref "U$8") (pin "G") (pinfunction "G_G") (pintype "passive"))
    )
    (net (code "116") (name "Net-(R34-Pad2)") (class "Default")
      (node (ref "R34") (pin "2") (pinfunction "2_2") (pintype "passive"))
      (node (ref "R35") (pin "2") (pinfunction "2_2") (pintype "passive"))
      (node (ref "U$11") (pin "G") (pinfunction "G_G") (pintype "passive"))
    )
    (net (code "117") (name "Net-(R37-Pad2)") (class "Default")
      (node (ref "R37") (pin "2") (pinfunction "2_2") (pintype "passive"))
      (node (ref "R38") (pin "2") (pinfunction "2_2") (pintype "passive"))
      (node (ref "U$14") (pin "G") (pinfunction "G_G") (pintype "passive"))
    )
    (net (code "118") (name "Net-(R40-Pad2)") (class "Default")
      (node (ref "R40") (pin "2") (pinfunction "2_2") (pintype "passive"))
      (node (ref "R41") (pin "2") (pinfunction "2_2") (pintype "passive"))
      (node (ref "U$17") (pin "G") (pinfunction "G_G") (pintype "passive"))
    )
    (net (code "119") (name "Net-(R43-Pad2)") (class "Default")
      (node (ref "R43") (pin "2") (pinfunction "2_2") (pintype "passive"))
      (node (ref "R44") (pin "2") (pinfunction "2_2") (pintype "passive"))
      (node (ref "U$20") (pin "G") (pinfunction "G_G") (pintype "passive"))
    )
    (net (code "120") (name "Net-(R47-Pad2)") (class "Default")
      (node (ref "R47") (pin "2") (pinfunction "2_2") (pintype "passive"))
      (node (ref "R48") (pin "2") (pinfunction "2_2") (pintype "passive"))
      (node (ref "U$23") (pin "G") (pinfunction "G_G") (pintype "passive"))
    )
    (net (code "121") (name "Net-(R50-Pad2)") (class "Default")
      (node (ref "R50") (pin "2") (pinfunction "2_2") (pintype "passive"))
      (node (ref "R51") (pin "2") (pinfunction "2_2") (pintype "passive"))
      (node (ref "U$26") (pin "G") (pinfunction "G_G") (pintype "passive"))
    )
    (net (code "122") (name "Net-(R53-Pad2)") (class "Default")
      (node (ref "R53") (pin "2") (pinfunction "2_2") (pintype "passive"))
      (node (ref "R54") (pin "2") (pinfunction "2_2") (pintype "passive"))
      (node (ref "U$29") (pin "G") (pinfunction "G_G") (pintype "passive"))
    )
    (net (code "123") (name "Net-(R56-Pad2)") (class "Default")
      (node (ref "R56") (pin "2") (pinfunction "2_2") (pintype "passive"))
      (node (ref "R57") (pin "2") (pinfunction "2_2") (pintype "passive"))
      (node (ref "U$32") (pin "G") (pinfunction "G_G") (pintype "passive"))
    )
    (net (code "124") (name "Net-(R66-Pad2)") (class "Default")
      (node (ref "R66") (pin "2") (pinfunction "2_2") (pintype "passive"))
      (node (ref "U$35") (pin "D") (pinfunction "D_D") (pintype "passive"))
    )
    (net (code "125") (name "Net-(R67-Pad2)") (class "Default")
      (node (ref "R67") (pin "2") (pinfunction "2_2") (pintype "passive"))
      (node (ref "R69") (pin "2") (pinfunction "2_2") (pintype "passive"))
      (node (ref "U$35") (pin "G") (pinfunction "G_G") (pintype "passive"))
    )
    (net (code "126") (name "Net-(R87-Pad1)") (class "Default")
      (node (ref "R87") (pin "1") (pinfunction "1_1") (pintype "passive"))
      (node (ref "R88") (pin "1") (pinfunction "1_1") (pintype "passive"))
      (node (ref "U$39") (pin "G") (pinfunction "G_G") (pintype "passive"))
    )
    (net (code "127") (name "Net-(R89A-2)") (class "Default")
      (node (ref "R89") (pin "8") (pinfunction "2_8") (pintype "passive"))
      (node (ref "U$1") (pin "B_12") (pinfunction "C_B_12") (pintype "passive"))
    )
    (net (code "128") (name "Net-(R89B-1)") (class "Default")
      (node (ref "R89") (pin "1") (pinfunction "1_1") (pintype "passive"))
      (node (ref "R89") (pin "2") (pinfunction "1_2") (pintype "passive"))
      (node (ref "R89") (pin "3") (pinfunction "1_3") (pintype "passive"))
      (node (ref "R89") (pin "4") (pinfunction "1_4") (pintype "passive"))
      (node (ref "U$39") (pin "D") (pinfunction "D_D") (pintype "passive"))
    )
    (net (code "129") (name "Net-(R89B-2)") (class "Default")
      (node (ref "R89") (pin "7") (pinfunction "2_7") (pintype "passive"))
      (node (ref "U$1") (pin "B_10") (pinfunction "C_B_10") (pintype "passive"))
    )
    (net (code "130") (name "Net-(R89C-2)") (class "Default")
      (node (ref "R89") (pin "6") (pinfunction "2_6") (pintype "passive"))
      (node (ref "U$1") (pin "T_10") (pinfunction "C_T_10") (pintype "passive"))
    )
    (net (code "131") (name "Net-(R89D-2)") (class "Default")
      (node (ref "R89") (pin "5") (pinfunction "2_5") (pintype "passive"))
      (node (ref "U$1") (pin "T_12") (pinfunction "C_T_12") (pintype "passive"))
    )
    (net (code "132") (name "Net-(SERVO1B-S)") (class "Default")
      (node (ref "R65") (pin "2") (pinfunction "2_2") (pintype "passive"))
      (node (ref "SERVO1") (pin "2") (pinfunction "S_2") (pintype "passive"))
      (node (ref "SERVO2") (pin "2") (pinfunction "S_2") (pintype "passive"))
    )
    (net (code "133") (name "Net-(U$6-P$1)") (class "Default")
      (node (ref "LED6") (pin "C") (pinfunction "C_C") (pintype "passive"))
      (node (ref "U$5") (pin "D") (pinfunction "D_D") (pintype "passive"))
      (node (ref "U$6") (pin "P$2") (pinfunction "P$1_P$2") (pintype "bidirectional"))
      (node (ref "U$7") (pin "A") (pinfunction "A_A") (pintype "passive"))
    )
    (net (code "134") (name "Net-(U$9-P$1)") (class "Default")
      (node (ref "LED7") (pin "C") (pinfunction "C_C") (pintype "passive"))
      (node (ref "U$10") (pin "A") (pinfunction "A_A") (pintype "passive"))
      (node (ref "U$8") (pin "D") (pinfunction "D_D") (pintype "passive"))
      (node (ref "U$9") (pin "P$2") (pinfunction "P$1_P$2") (pintype "bidirectional"))
    )
    (net (code "135") (name "Net-(U$12-P$1)") (class "Default")
      (node (ref "LED8") (pin "C") (pinfunction "C_C") (pintype "passive"))
      (node (ref "U$11") (pin "D") (pinfunction "D_D") (pintype "passive"))
      (node (ref "U$12") (pin "P$2") (pinfunction "P$1_P$2") (pintype "bidirectional"))
      (node (ref "U$13") (pin "A") (pinfunction "A_A") (pintype "passive"))
    )
    (net (code "136") (name "Net-(U$15-P$1)") (class "Default")
      (node (ref "LED9") (pin "C") (pinfunction "C_C") (pintype "passive"))
      (node (ref "U$14") (pin "D") (pinfunction "D_D") (pintype "passive"))
      (node (ref "U$15") (pin "P$2") (pinfunction "P$1_P$2") (pintype "bidirectional"))
      (node (ref "U$16") (pin "A") (pinfunction "A_A") (pintype "passive"))
    )
    (net (code "137") (name "Net-(U$18-P$1)") (class "Default")
      (node (ref "LED10") (pin "C") (pinfunction "C_C") (pintype "passive"))
      (node (ref "U$17") (pin "D") (pinfunction "D_D") (pintype "passive"))
      (node (ref "U$18") (pin "P$2") (pinfunction "P$1_P$2") (pintype "bidirectional"))
      (node (ref "U$19") (pin "A") (pinfunction "A_A") (pintype "passive"))
    )
    (net (code "138") (name "Net-(U$21-P$1)") (class "Default")
      (node (ref "LED11") (pin "C") (pinfunction "C_C") (pintype "passive"))
      (node (ref "U$20") (pin "D") (pinfunction "D_D") (pintype "passive"))
      (node (ref "U$21") (pin "P$2") (pinfunction "P$1_P$2") (pintype "bidirectional"))
      (node (ref "U$22") (pin "A") (pinfunction "A_A") (pintype "passive"))
    )
    (net (code "139") (name "Net-(U$24-P$1)") (class "Default")
      (node (ref "LED12") (pin "C") (pinfunction "C_C") (pintype "passive"))
      (node (ref "U$23") (pin "D") (pinfunction "D_D") (pintype "passive"))
      (node (ref "U$24") (pin "P$2") (pinfunction "P$1_P$2") (pintype "bidirectional"))
      (node (ref "U$25") (pin "A") (pinfunction "A_A") (pintype "passive"))
    )
    (net (code "140") (name "Net-(U$27-P$1)") (class "Default")
      (node (ref "LED13") (pin "C") (pinfunction "C_C") (pintype "passive"))
      (node (ref "U$26") (pin "D") (pinfunction "D_D") (pintype "passive"))
      (node (ref "U$27") (pin "P$2") (pinfunction "P$1_P$2") (pintype "bidirectional"))
      (node (ref "U$28") (pin "A") (pinfunction "A_A") (pintype "passive"))
    )
    (net (code "141") (name "Net-(U$30-P$1)") (class "Default")
      (node (ref "LED14") (pin "C") (pinfunction "C_C") (pintype "passive"))
      (node (ref "U$29") (pin "D") (pinfunction "D_D") (pintype "passive"))
      (node (ref "U$30") (pin "P$2") (pinfunction "P$1_P$2") (pintype "bidirectional"))
      (node (ref "U$31") (pin "A") (pinfunction "A_A") (pintype "passive"))
    )
    (net (code "142") (name "Net-(U$33-P$1)") (class "Default")
      (node (ref "LED15") (pin "C") (pinfunction "C_C") (pintype "passive"))
      (node (ref "U$32") (pin "D") (pinfunction "D_D") (pintype "passive"))
      (node (ref "U$33") (pin "P$2") (pinfunction "P$1_P$2") (pintype "bidirectional"))
      (node (ref "U$34") (pin "A") (pinfunction "A_A") (pintype "passive"))
    )
    (net (code "143") (name "OP-1") (class "Default")
      (node (ref "MCU") (pin "95") (pinfunction "PD30_95") (pintype "bidirectional"))
      (node (ref "R68") (pin "4") (pinfunction "1_4") (pintype "passive"))
      (node (ref "V2") (pin "12") (pinfunction "A_12") (pintype "input"))
    )
    (net (code "144") (name "OP-1S") (class "Default")
      (node (ref "R3") (pin "1") (pinfunction "1_1") (pintype "passive"))
      (node (ref "V2") (pin "11") (pinfunction "Y_11") (pintype "output"))
    )
    (net (code "145") (name "OP-2") (class "Default")
      (node (ref "MCU") (pin "94") (pinfunction "PD29_94") (pintype "bidirectional"))
      (node (ref "R68") (pin "3") (pinfunction "1_3") (pintype "passive"))
      (node (ref "V2") (pin "9") (pinfunction "A_9") (pintype "input"))
    )
    (net (code "146") (name "OP-2S") (class "Default")
      (node (ref "R31") (pin "1") (pinfunction "1_1") (pintype "passive"))
      (node (ref "V2") (pin "8") (pinfunction "Y_8") (pintype "output"))
    )
    (net (code "147") (name "OP-3") (class "Default")
      (node (ref "MCU") (pin "93") (pinfunction "PD28_93") (pintype "bidirectional"))
      (node (ref "R68") (pin "2") (pinfunction "1_2") (pintype "passive"))
      (node (ref "V2") (pin "4") (pinfunction "A_4") (pintype "input"))
    )
    (net (code "148") (name "OP-3S") (class "Default")
      (node (ref "R34") (pin "1") (pinfunction "1_1") (pintype "passive"))
      (node (ref "V2") (pin "6") (pinfunction "Y_6") (pintype "output"))
    )
    (net (code "149") (name "OP-4") (class "Default")
      (node (ref "MCU") (pin "92") (pinfunction "PD27_92") (pintype "bidirectional"))
      (node (ref "R68") (pin "1") (pinfunction "1_1") (pintype "passive"))
      (node (ref "V2") (pin "1") (pinfunction "A_1") (pintype "input"))
    )
    (net (code "150") (name "OP-4S") (class "Default")
      (node (ref "R37") (pin "1") (pinfunction "1_1") (pintype "passive"))
      (node (ref "V2") (pin "3") (pinfunction "Y_3") (pintype "output"))
    )
    (net (code "151") (name "OP-5") (class "Default")
      (node (ref "MCU") (pin "91") (pinfunction "PD24_91") (pintype "bidirectional"))
      (node (ref "R63") (pin "1") (pinfunction "1_1") (pintype "passive"))
      (node (ref "V1") (pin "9") (pinfunction "A_9") (pintype "input"))
    )
    (net (code "152") (name "OP-5S") (class "Default")
      (node (ref "R40") (pin "1") (pinfunction "1_1") (pintype "passive"))
      (node (ref "V1") (pin "8") (pinfunction "Y_8") (pintype "output"))
    )
    (net (code "153") (name "OP-6") (class "Default")
      (node (ref "MCU") (pin "85") (pinfunction "PD12_85") (pintype "bidirectional"))
      (node (ref "R62") (pin "1") (pinfunction "1_1") (pintype "passive"))
      (node (ref "V1") (pin "12") (pinfunction "A_12") (pintype "input"))
    )
    (net (code "154") (name "OP-6S") (class "Default")
      (node (ref "R43") (pin "1") (pinfunction "1_1") (pintype "passive"))
      (node (ref "V1") (pin "11") (pinfunction "Y_11") (pintype "output"))
    )
    (net (code "155") (name "OP-7") (class "Default")
      (node (ref "MCU") (pin "84") (pinfunction "PD11_84") (pintype "bidirectional"))
      (node (ref "R61") (pin "1") (pinfunction "1_1") (pintype "passive"))
      (node (ref "V1") (pin "4") (pinfunction "A_4") (pintype "input"))
    )
    (net (code "156") (name "OP-7S") (class "Default")
      (node (ref "R47") (pin "1") (pinfunction "1_1") (pintype "passive"))
      (node (ref "V1") (pin "6") (pinfunction "Y_6") (pintype "output"))
    )
    (net (code "157") (name "OP-8") (class "Default")
      (node (ref "MCU") (pin "81") (pinfunction "PD10_81") (pintype "bidirectional"))
      (node (ref "R60") (pin "1") (pinfunction "1_1") (pintype "passive"))
      (node (ref "V1") (pin "1") (pinfunction "A_1") (pintype "input"))
    )
    (net (code "158") (name "OP-8S") (class "Default")
      (node (ref "R50") (pin "1") (pinfunction "1_1") (pintype "passive"))
      (node (ref "V1") (pin "3") (pinfunction "Y_3") (pintype "output"))
    )
    (net (code "159") (name "OP-9") (class "Default")
      (node (ref "MCU") (pin "80") (pinfunction "PD9_80") (pintype "bidirectional"))
      (node (ref "R59") (pin "1") (pinfunction "1_1") (pintype "passive"))
      (node (ref "V3") (pin "4") (pinfunction "A_4") (pintype "input"))
    )
    (net (code "160") (name "OP-9S") (class "Default")
      (node (ref "R53") (pin "1") (pinfunction "1_1") (pintype "passive"))
      (node (ref "V3") (pin "6") (pinfunction "Y_6") (pintype "output"))
    )
    (net (code "161") (name "OP-10") (class "Default")
      (node (ref "MCU") (pin "79") (pinfunction "PD8_79") (pintype "bidirectional"))
      (node (ref "R4") (pin "1") (pinfunction "1_1") (pintype "passive"))
      (node (ref "V3") (pin "1") (pinfunction "A_1") (pintype "input"))
    )
    (net (code "162") (name "OP-10S") (class "Default")
      (node (ref "R56") (pin "1") (pinfunction "1_1") (pintype "passive"))
      (node (ref "V3") (pin "3") (pinfunction "Y_3") (pintype "output"))
    )
    (net (code "166") (name "OP1-FAN_IN") (class "Default")
      (node (ref "MCU") (pin "61") (pinfunction "PC13_61") (pintype "bidirectional"))
      (node (ref "R64") (pin "1") (pinfunction "1_1") (pintype "passive"))
      (node (ref "U$3") (pin "4") (pinfunction "P$1_4") (pintype "bidirectional"))
    )
    (net (code "167") (name "OP1-FAN_TAC") (class "Default")
      (node (ref "FAN1") (pin "3") (pinfunction "S_3") (pintype "passive"))
      (node (ref "MCU") (pin "76") (pinfunction "PD2_76") (pintype "bidirectional"))
    )
    (net (code "168") (name "OP1-SRV_IN") (class "Default")
      (node (ref "MCU") (pin "59") (pinfunction "PC11_59") (pintype "bidirectional"))
      (node (ref "R65") (pin "1") (pinfunction "1_1") (pintype "passive"))
      (node (ref "U$3") (pin "3") (pinfunction "P$1_3") (pintype "bidirectional"))
    )
    (net (code "169") (name "RESCON(S)") (class "Default")
      (node (ref "MCU") (pin "45") (pinfunction "PB22_45") (pintype "bidirectional"))
      (node (ref "R19") (pin "1") (pinfunction "1_1") (pintype "passive"))
      (node (ref "RESCON") (pin "P$1") (pinfunction "P$2_P$1") (pintype "bidirectional"))
    )
    (net (code "170") (name "START(S)") (class "Default")
      (node (ref "C23") (pin "1") (pinfunction "1_1") (pintype "passive"))
      (node (ref "MCU") (pin "100") (pinfunction "PB3_100") (pintype "bidirectional"))
      (node (ref "R20") (pin "1") (pinfunction "1_1") (pintype "passive"))
      (node (ref "START") (pin "P$1") (pinfunction "P$2_P$1") (pintype "bidirectional"))
    )
    (net (code "171") (name "SYS_OK") (class "Default")
      (node (ref "MCU") (pin "99") (pinfunction "PB2_99") (pintype "bidirectional"))
      (node (ref "R2") (pin "2") (pinfunction "2_2") (pintype "passive"))
      (node (ref "R67") (pin "1") (pinfunction "1_1") (pintype "passive"))
      (node (ref "SYS_OK") (pin "P$1") (pinfunction "P$2_P$1") (pintype "bidirectional"))
      (node (ref "V1") (pin "10") (pinfunction "B_10") (pintype "input"))
      (node (ref "V1") (pin "13") (pinfunction "B_13") (pintype "input"))
      (node (ref "V1") (pin "2") (pinfunction "B_2") (pintype "input"))
      (node (ref "V1") (pin "5") (pinfunction "B_5") (pintype "input"))
      (node (ref "V2") (pin "10") (pinfunction "B_10") (pintype "input"))
      (node (ref "V2") (pin "13") (pinfunction "B_13") (pintype "input"))
      (node (ref "V2") (pin "2") (pinfunction "B_2") (pintype "input"))
      (node (ref "V2") (pin "5") (pinfunction "B_5") (pintype "input"))
      (node (ref "V3") (pin "2") (pinfunction "B_2") (pintype "input"))
      (node (ref "V3") (pin "5") (pinfunction "B_5") (pintype "input"))
    )
    (net (code "172") (name "TANKPRES_S+") (class "Default")
      (node (ref "R21") (pin "2") (pinfunction "2_2") (pintype "passive"))
      (node (ref "R71") (pin "2") (pinfunction "2_2") (pintype "passive"))
      (node (ref "TANKPRES") (pin "2") (pinfunction "2_2") (pintype "passive"))
    )
    (net (code "173") (name "TANKPRES_S+(S)") (class "Default")
      (node (ref "R26") (pin "6") (pinfunction "2_6") (pintype "passive"))
      (node (ref "R71") (pin "1") (pinfunction "1_1") (pintype "passive"))
      (node (ref "R72") (pin "2") (pinfunction "2_2") (pintype "passive"))
    )
    (net (code "174") (name "TANKPRES_S-") (class "Default")
      (node (ref "R21") (pin "1") (pinfunction "1_1") (pintype "passive"))
      (node (ref "R77") (pin "2") (pinfunction "2_2") (pintype "passive"))
      (node (ref "TANKPRES") (pin "3") (pinfunction "3_3") (pintype "passive"))
    )
    (net (code "175") (name "TANKPRES_S-(S)") (class "Default")
      (node (ref "R29") (pin "1") (pinfunction "1_1") (pintype "passive"))
      (node (ref "R77") (pin "1") (pinfunction "1_1") (pintype "passive"))
      (node (ref "R78") (pin "2") (pinfunction "2_2") (pintype "passive"))
    )
    (net (code "176") (name "TCK") (class "Default")
      (node (ref "JTAG") (pin "1") (pinfunction "1_1") (pintype "passive"))
      (node (ref "MCU") (pin "1") (pinfunction "PA0_1") (pintype "bidirectional"))
    )
    (net (code "177") (name "TDI") (class "Default")
      (node (ref "JTAG") (pin "9") (pinfunction "9_9") (pintype "passive"))
      (node (ref "MCU") (pin "2") (pinfunction "PA1_2") (pintype "bidirectional"))
    )
    (net (code "178") (name "TDO") (class "Default")
      (node (ref "JTAG") (pin "3") (pinfunction "3_3") (pintype "passive"))
      (node (ref "MCU") (pin "3") (pinfunction "PA2_3") (pintype "bidirectional"))
    )
    (net (code "179") (name "TMS") (class "Default")
      (node (ref "JTAG") (pin "5") (pinfunction "5_5") (pintype "passive"))
      (node (ref "MCU") (pin "4") (pinfunction "PA3_4") (pintype "bidirectional"))
    )
    (net (code "180") (name "USB_N") (class "Default")
      (node (ref "JP2") (pin "D-") (pinfunction "D-_D-") (pintype "bidirectional"))
      (node (ref "MCU") (pin "35") (pinfunction "DM_35") (pintype "bidirectional"))
    )
    (net (code "181") (name "USB_P") (class "Default")
      (node (ref "JP2") (pin "D+") (pinfunction "D+_D+") (pintype "bidirectional"))
      (node (ref "MCU") (pin "36") (pinfunction "DP_36") (pintype "bidirectional"))
    )
    (net (code "182") (name "USB_VBUS") (class "Default")
      (node (ref "JP2") (pin "VBUS") (pinfunction "VBUS_VBUS") (pintype "bidirectional"))
      (node (ref "MCU") (pin "34") (pinfunction "VBUS_34") (pintype "bidirectional"))
    )
    (net (code "183") (name "VCC") (class "Default")
      (node (ref "4-NMOS") (pin "11") (pinfunction "11_11") (pintype "passive"))
      (node (ref "4-NMOS1") (pin "11") (pinfunction "11_11") (pintype "passive"))
      (node (ref "C1") (pin "1") (pinfunction "1_1") (pintype "passive"))
      (node (ref "C11") (pin "+") (pinfunction "+_+") (pintype "passive"))
      (node (ref "C13") (pin "1") (pinfunction "1_1") (pintype "passive"))
      (node (ref "C15") (pin "+") (pinfunction "+_+") (pintype "passive"))
      (node (ref "C17") (pin "1") (pinfunction "1_1") (pintype "passive"))
      (node (ref "C18") (pin "1") (pinfunction "1_1") (pintype "passive"))
      (node (ref "C4") (pin "1") (pinfunction "1_1") (pintype "passive"))
      (node (ref "C5") (pin "1") (pinfunction "1_1") (pintype "passive"))
      (node (ref "CAN-EXP") (pin "1") (pinfunction "S_1") (pintype "passive"))
      (node (ref "CAPCON/VOLT") (pin "3") (pinfunction "3_3") (pintype "passive"))
      (node (ref "D0") (pin "A") (pinfunction "A_A") (pintype "passive"))
      (node (ref "D1") (pin "A") (pinfunction "A_A") (pintype "passive"))
      (node (ref "D2") (pin "A") (pinfunction "A_A") (pintype "passive"))
      (node (ref "D3") (pin "A") (pinfunction "A_A") (pintype "passive"))
      (node (ref "EXT-LEDS") (pin "1") (pinfunction "S_1") (pintype "passive"))
      (node (ref "FCCON/VOLT") (pin "3") (pinfunction "3_3") (pintype "passive"))
      (node (ref "JP1") (pin "1") (pinfunction "1_1") (pintype "passive"))
      (node (ref "JP3") (pin "1") (pinfunction "1_1") (pintype "passive"))
      (node (ref "JTAG") (pin "4") (pinfunction "4_4") (pintype "passive"))
      (node (ref "JTAG") (pin "7") (pinfunction "7_7") (pintype "passive"))
      (node (ref "L1") (pin "2") (pinfunction "2_2") (pintype "passive"))
      (node (ref "LD39300-NNP") (pin "3") (pinfunction "IN_3") (pintype "input"))
      (node (ref "LERROR") (pin "A") (pinfunction "A_A") (pintype "passive"))
      (node (ref "LRUN") (pin "A") (pinfunction "A_A") (pintype "passive"))
      (node (ref "LSTART") (pin "A") (pinfunction "A_A") (pintype "passive"))
      (node (ref "LSTOP") (pin "A") (pinfunction "A_A") (pintype "passive"))
      (node (ref "MCU") (pin "38") (pinfunction "VDD_5_38") (pintype "bidirectional"))
      (node (ref "MCU") (pin "5") (pinfunction "VDDIO1_5") (pintype "bidirectional"))
      (node (ref "MCU") (pin "53") (pinfunction "VDDIO2_53") (pintype "bidirectional"))
      (node (ref "MCU") (pin "82") (pinfunction "VDDIO3_82") (pintype "bidirectional"))
      (node (ref "POWER") (pin "15") (pinfunction "15_15") (pintype "passive"))
      (node (ref "POWER") (pin "16") (pinfunction "16_16") (pintype "passive"))
      (node (ref "R23") (pin "2") (pinfunction "2_2") (pintype "passive"))
      (node (ref "R45") (pin "2") (pinfunction "2_2") (pintype "passive"))
      (node (ref "R70") (pin "1") (pinfunction "1_1") (pintype "passive"))
      (node (ref "R70") (pin "2") (pinfunction "1_2") (pintype "passive"))
      (node (ref "R70") (pin "3") (pinfunction "1_3") (pintype "passive"))
      (node (ref "R70") (pin "4") (pinfunction "1_4") (pintype "passive"))
      (node (ref "R9") (pin "1") (pinfunction "1_1") (pintype "passive"))
      (node (ref "R9") (pin "2") (pinfunction "1_2") (pintype "passive"))
      (node (ref "RESCON") (pin "P$2") (pinfunction "P$1_P$2") (pintype "bidirectional"))
      (node (ref "SERVO1") (pin "3") (pinfunction "S_3") (pintype "passive"))
      (node (ref "SERVO2") (pin "3") (pinfunction "S_3") (pintype "passive"))
      (node (ref "START") (pin "P$2") (pinfunction "P$1_P$2") (pintype "bidirectional"))
      (node (ref "U$2") (pin "9") (pinfunction "P$1_9") (pintype "bidirectional"))
      (node (ref "U$3") (pin "2") (pinfunction "P$1_2") (pintype "bidirectional"))
      (node (ref "U$36") (pin "3") (pinfunction "VDD/5V_3") (pintype "bidirectional"))
      (node (ref "U$4") (pin "3") (pinfunction "VDD/5V_3") (pintype "bidirectional"))
    )
    (net (code "184") (name "unconnected-(FAN2C-S-Pad3)") (class "Default")
      (node (ref "FAN2") (pin "3") (pinfunction "S_3") (pintype "passive"))
    )
    (net (code "185") (name "unconnected-(MCU-PA13-Pad19)") (class "Default")
      (node (ref "MCU") (pin "19") (pinfunction "PA13_19") (pintype "bidirectional"))
    )
    (net (code "186") (name "unconnected-(MCU-PA14-Pad20)") (class "Default")
      (node (ref "MCU") (pin "20") (pinfunction "PA14_20") (pintype "bidirectional"))
    )
    (net (code "187") (name "unconnected-(MCU-PA15-Pad21)") (class "Default")
      (node (ref "MCU") (pin "21") (pinfunction "PA15_21") (pintype "bidirectional"))
    )
    (net (code "188") (name "unconnected-(MCU-PA16-Pad22)") (class "Default")
      (node (ref "MCU") (pin "22") (pinfunction "PA16_22") (pintype "bidirectional"))
    )
    (net (code "189") (name "unconnected-(MCU-PB6-Pad9)") (class "Default")
      (node (ref "MCU") (pin "9") (pinfunction "PB6_9") (pintype "bidirectional"))
    )
    (net (code "190") (name "unconnected-(MCU-PC4-Pad55)") (class "Default")
      (node (ref "MCU") (pin "55") (pinfunction "PC4_55") (pintype "bidirectional"))
    )
    (net (code "191") (name "unconnected-(MCU-PC5-Pad56)") (class "Default")
      (node (ref "MCU") (pin "56") (pinfunction "PC5_56") (pintype "bidirectional"))
    )
    (net (code "192") (name "unconnected-(MCU-PD0-Pad74)") (class "Default")
      (node (ref "MCU") (pin "74") (pinfunction "PD0_74") (pintype "bidirectional"))
    )
    (net (code "193") (name "unconnected-(MCU-PD1-Pad75)") (class "Default")
      (node (ref "MCU") (pin "75") (pinfunction "PD1_75") (pintype "bidirectional"))
    )
    (net (code "194") (name "unconnected-(MCU-PD3-Pad77)") (class "Default")
      (node (ref "MCU") (pin "77") (pinfunction "PD3_77") (pintype "bidirectional"))
    )
    (net (code "195") (name "unconnected-(MCU-PD7-Pad78)") (class "Default")
      (node (ref "MCU") (pin "78") (pinfunction "PD7_78") (pintype "bidirectional"))
    )
    (net (code "196") (name "unconnected-(MCU-PD13-Pad86)") (class "Default")
      (node (ref "MCU") (pin "86") (pinfunction "PD13_86") (pintype "bidirectional"))
    )
    (net (code "197") (name "unconnected-(MCU-PD14-Pad87)") (class "Default")
      (node (ref "MCU") (pin "87") (pinfunction "PD14_87") (pintype "bidirectional"))
    )
    (net (code "198") (name "unconnected-(MCU-PD21-Pad88)") (class "Default")
      (node (ref "MCU") (pin "88") (pinfunction "PD21_88") (pintype "bidirectional"))
    )
    (net (code "199") (name "unconnected-(MCU-PD22-Pad89)") (class "Default")
      (node (ref "MCU") (pin "89") (pinfunction "PD22_89") (pintype "bidirectional"))
    )
    (net (code "200") (name "unconnected-(MCU-PD23-Pad90)") (class "Default")
      (node (ref "MCU") (pin "90") (pinfunction "PD23_90") (pintype "bidirectional"))
    )
    (net (code "201") (name "unconnected-(U$1A-3-PadB_3)") (class "Default")
      (node (ref "U$1") (pin "B_3") (pinfunction "3_B_3") (pintype "bidirectional"))
    )
    (net (code "202") (name "unconnected-(U$1A-4-PadB_4)") (class "Default")
      (node (ref "U$1") (pin "B_4") (pinfunction "4_B_4") (pintype "bidirectional"))
    )
    (net (code "203") (name "unconnected-(U$1A-5-PadB_5)") (class "Default")
      (node (ref "U$1") (pin "B_5") (pinfunction "5_B_5") (pintype "bidirectional"))
    )
    (net (code "204") (name "unconnected-(U$1A-7-PadB_7)") (class "Default")
      (node (ref "U$1") (pin "B_7") (pinfunction "7_B_7") (pintype "bidirectional"))
    )
    (net (code "205") (name "unconnected-(U$1D-3-PadT_3)") (class "Default")
      (node (ref "U$1") (pin "T_3") (pinfunction "3_T_3") (pintype "bidirectional"))
    )
    (net (code "206") (name "unconnected-(U$1D-4-PadT_4)") (class "Default")
      (node (ref "U$1") (pin "T_4") (pinfunction "4_T_4") (pintype "bidirectional"))
    )
    (net (code "207") (name "unconnected-(U$1D-5-PadT_5)") (class "Default")
      (node (ref "U$1") (pin "T_5") (pinfunction "5_T_5") (pintype "bidirectional"))
    )
    (net (code "208") (name "unconnected-(U$1D-7-PadT_7)") (class "Default")
      (node (ref "U$1") (pin "T_7") (pinfunction "7_T_7") (pintype "bidirectional"))
    )
    (net (code "209") (name "unconnected-(U$4-VREF-Pad5)") (class "Default")
      (node (ref "U$4") (pin "5") (pinfunction "VREF_5") (pintype "bidirectional"))
    )
    (net (code "210") (name "unconnected-(U$36-VREF-Pad5)") (class "Default")
      (node (ref "U$36") (pin "5") (pinfunction "VREF_5") (pintype "bidirectional"))
    )
  )
)
